# Schematic_SF_13_12_2020_V8.net
KiCad netlist of a schematic drawn in EAGLE
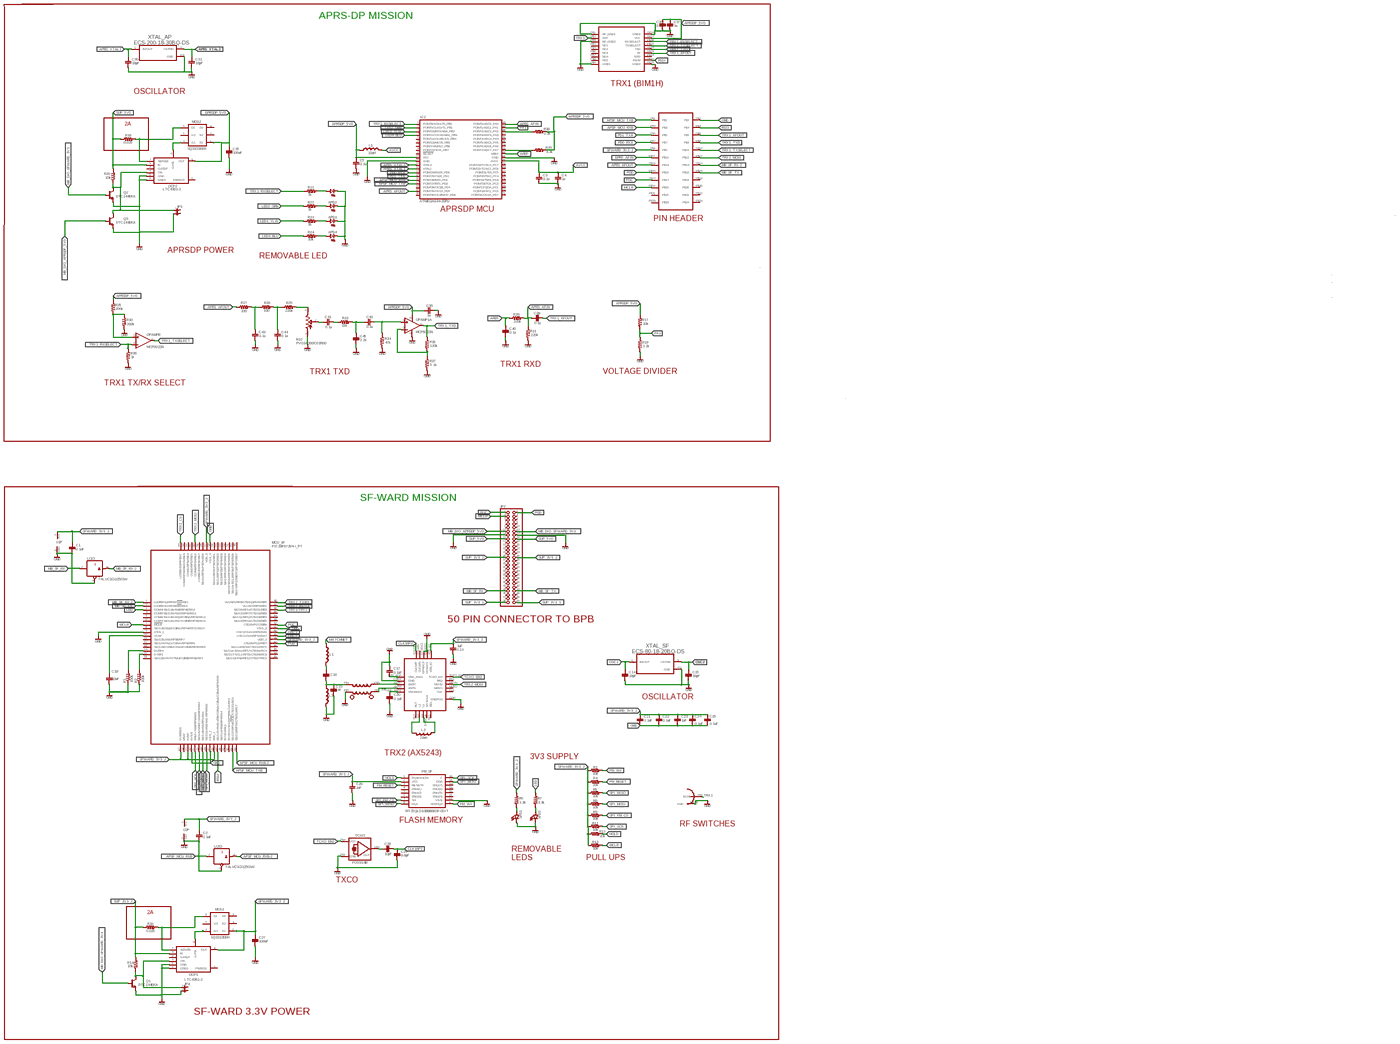
[diagram p0: schematic, sheet 1, overview]
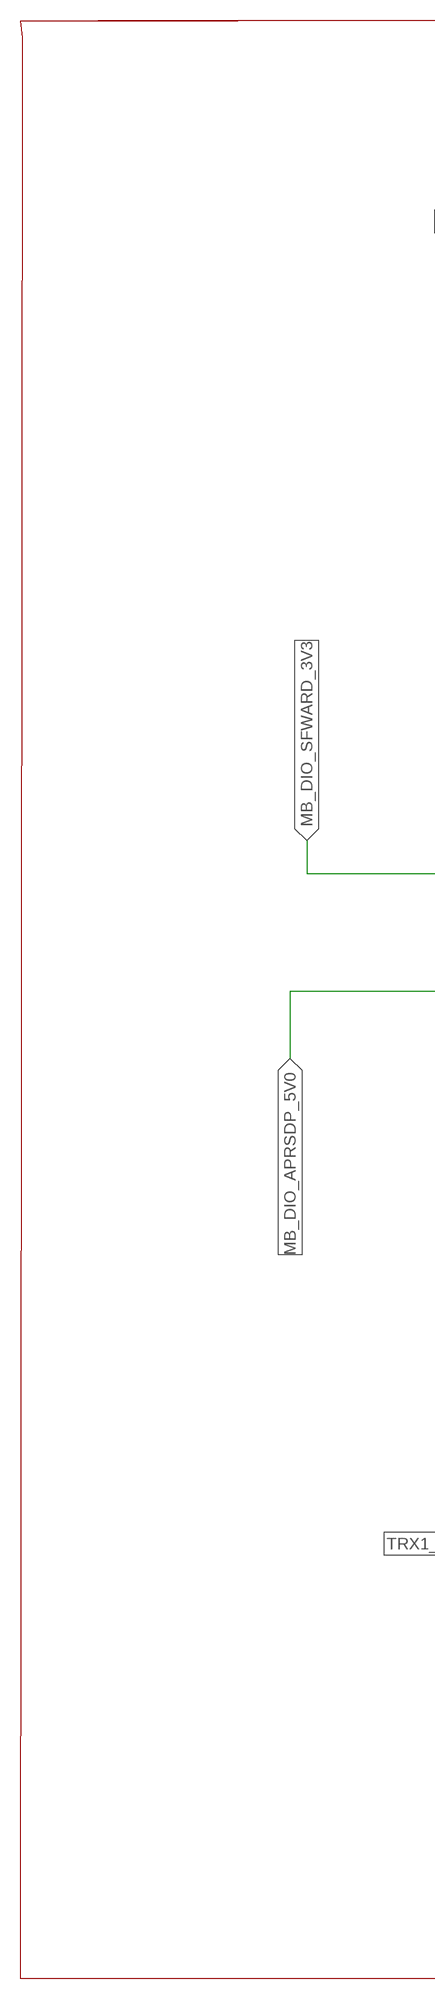
[diagram p1: schematic, sheet 1, part 1 of 4]
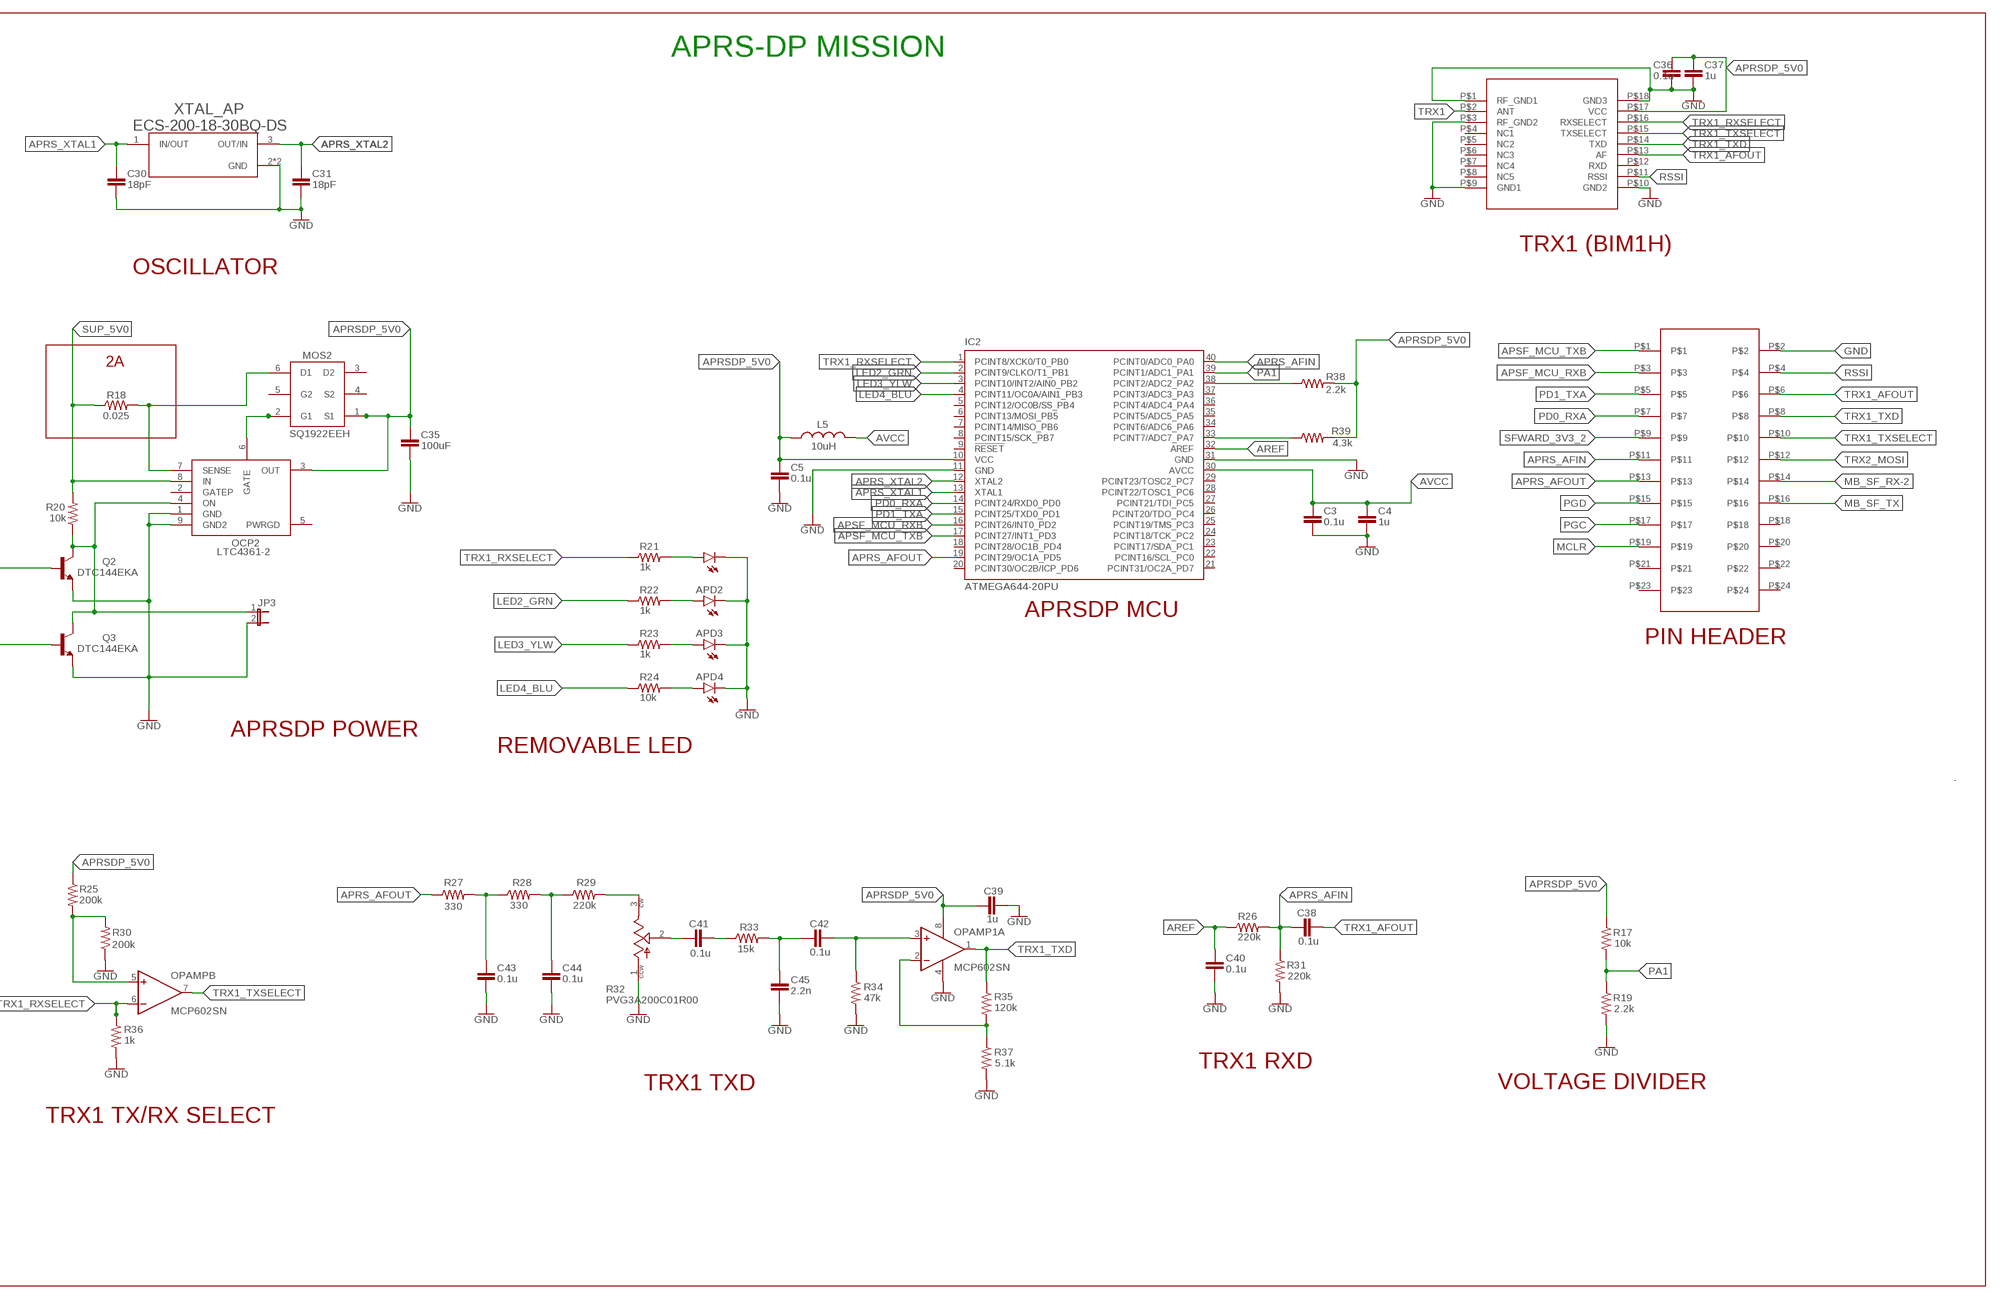
[diagram p2: schematic, sheet 1, part 2 of 4]
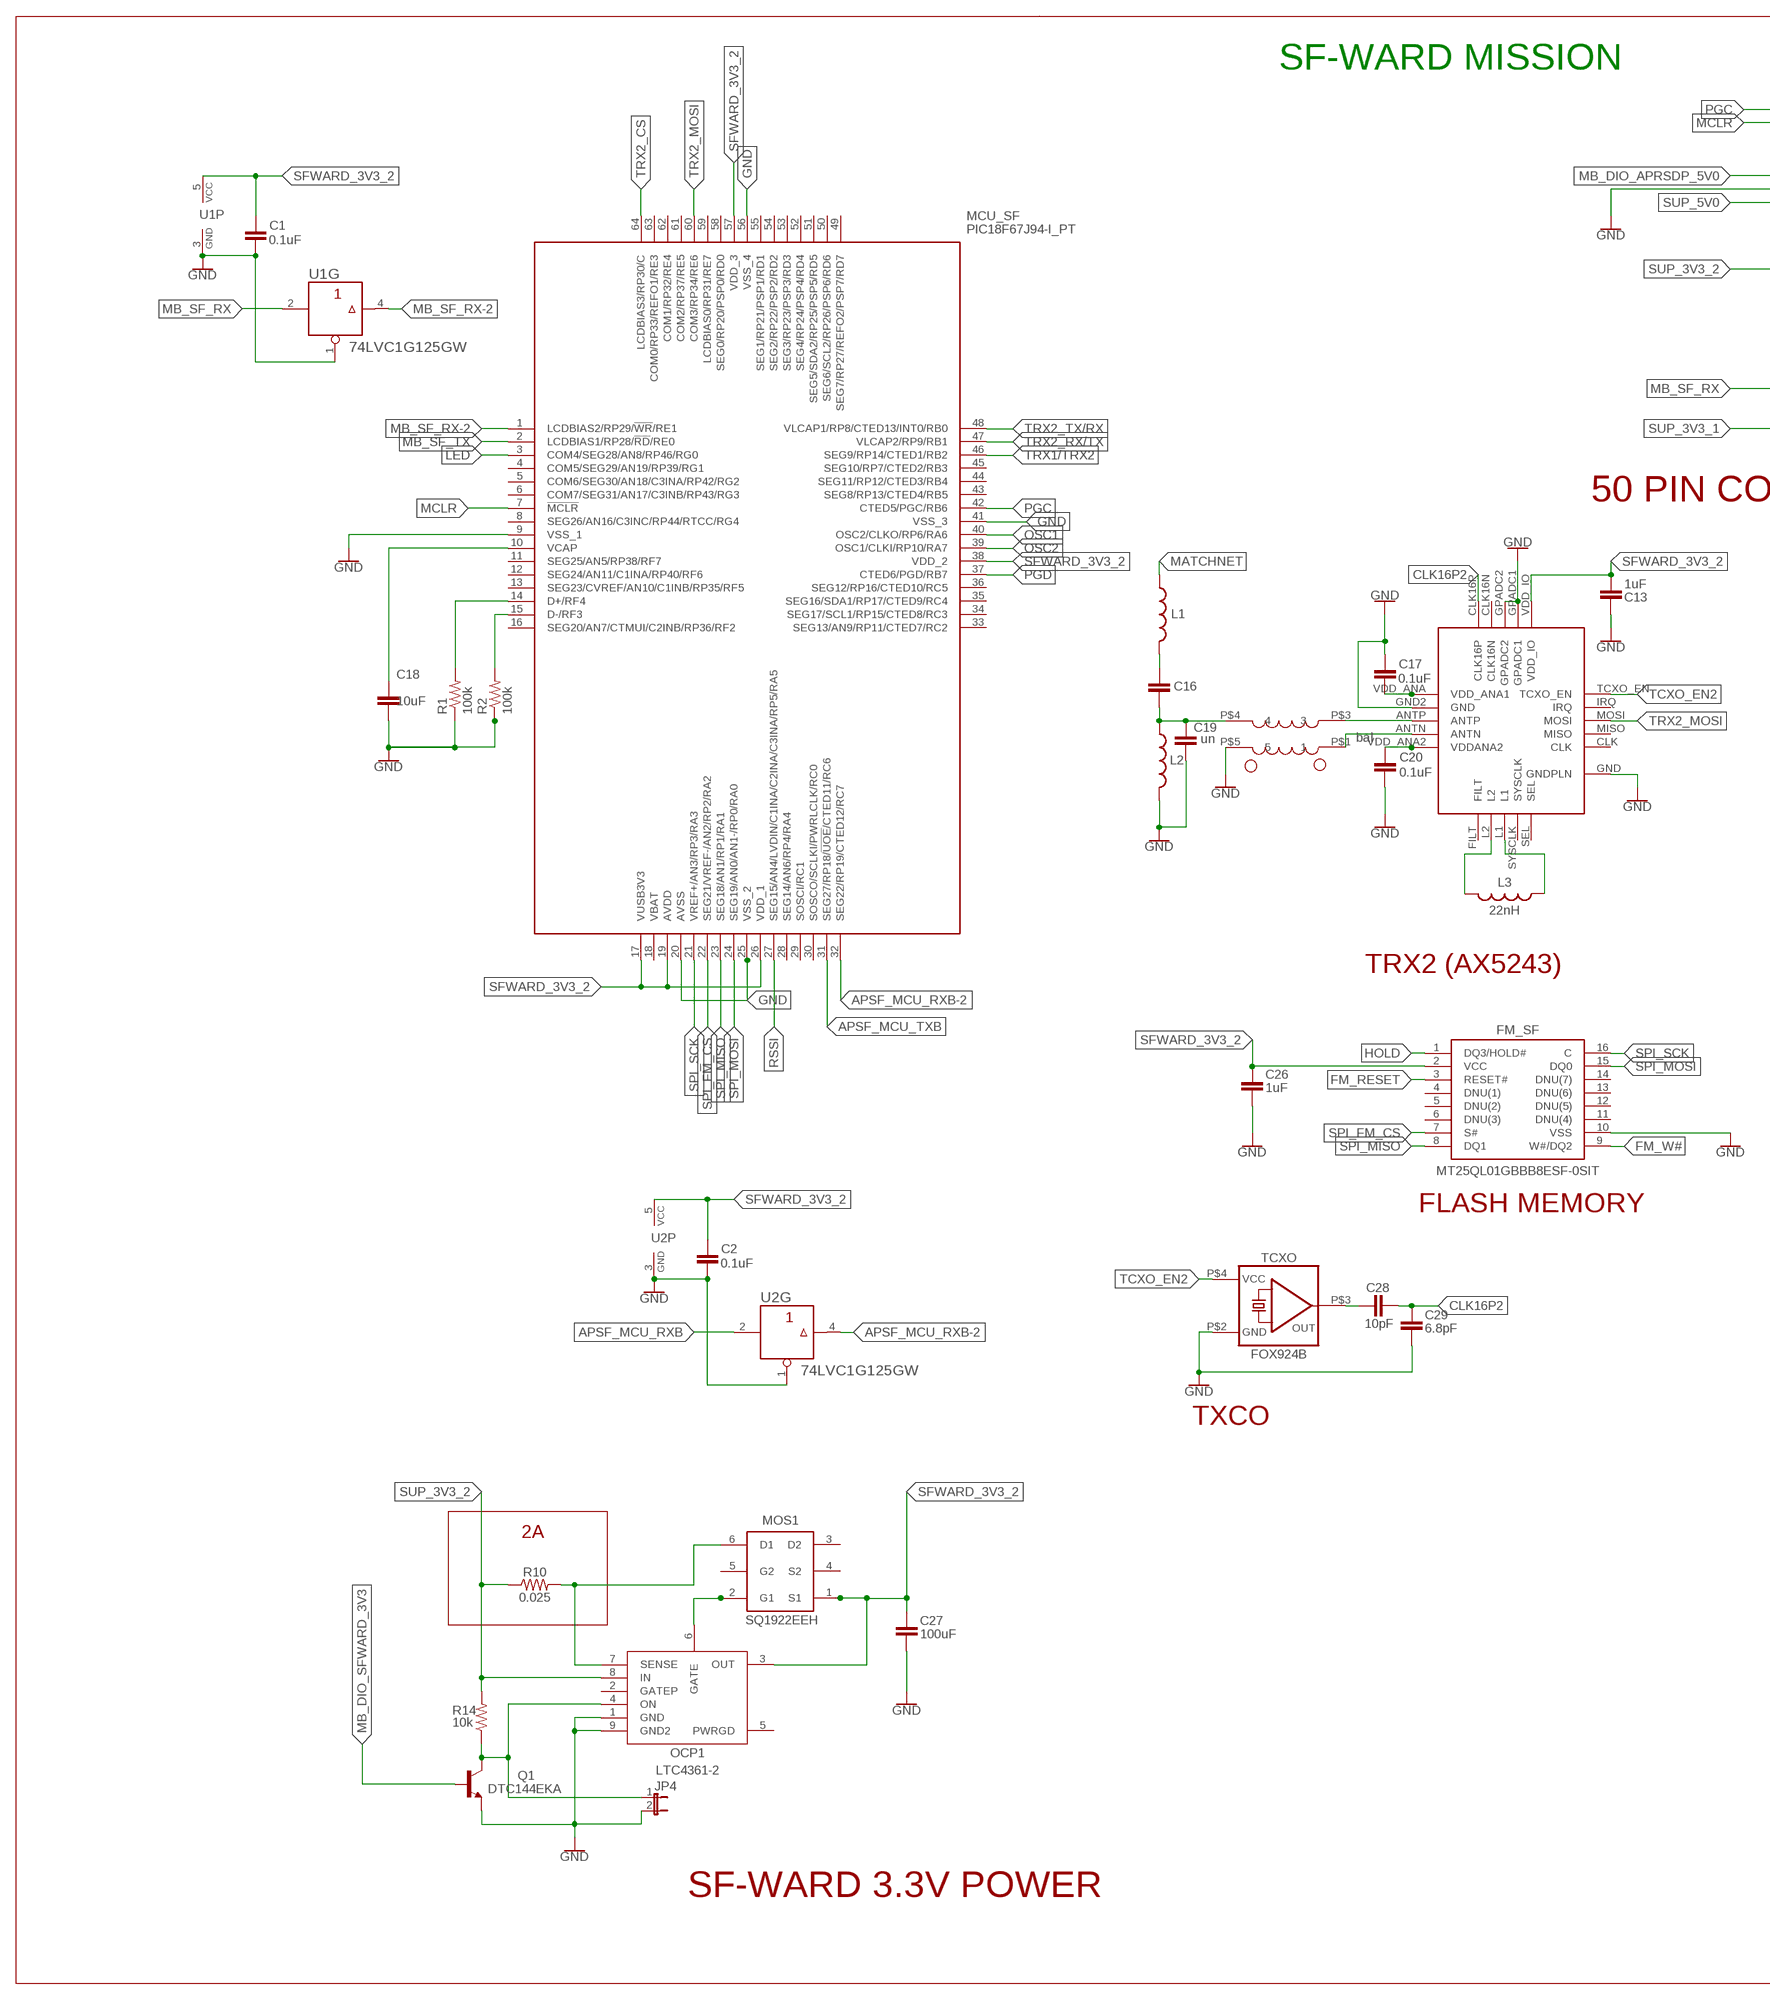
[diagram p3: schematic, sheet 1, part 3 of 4]
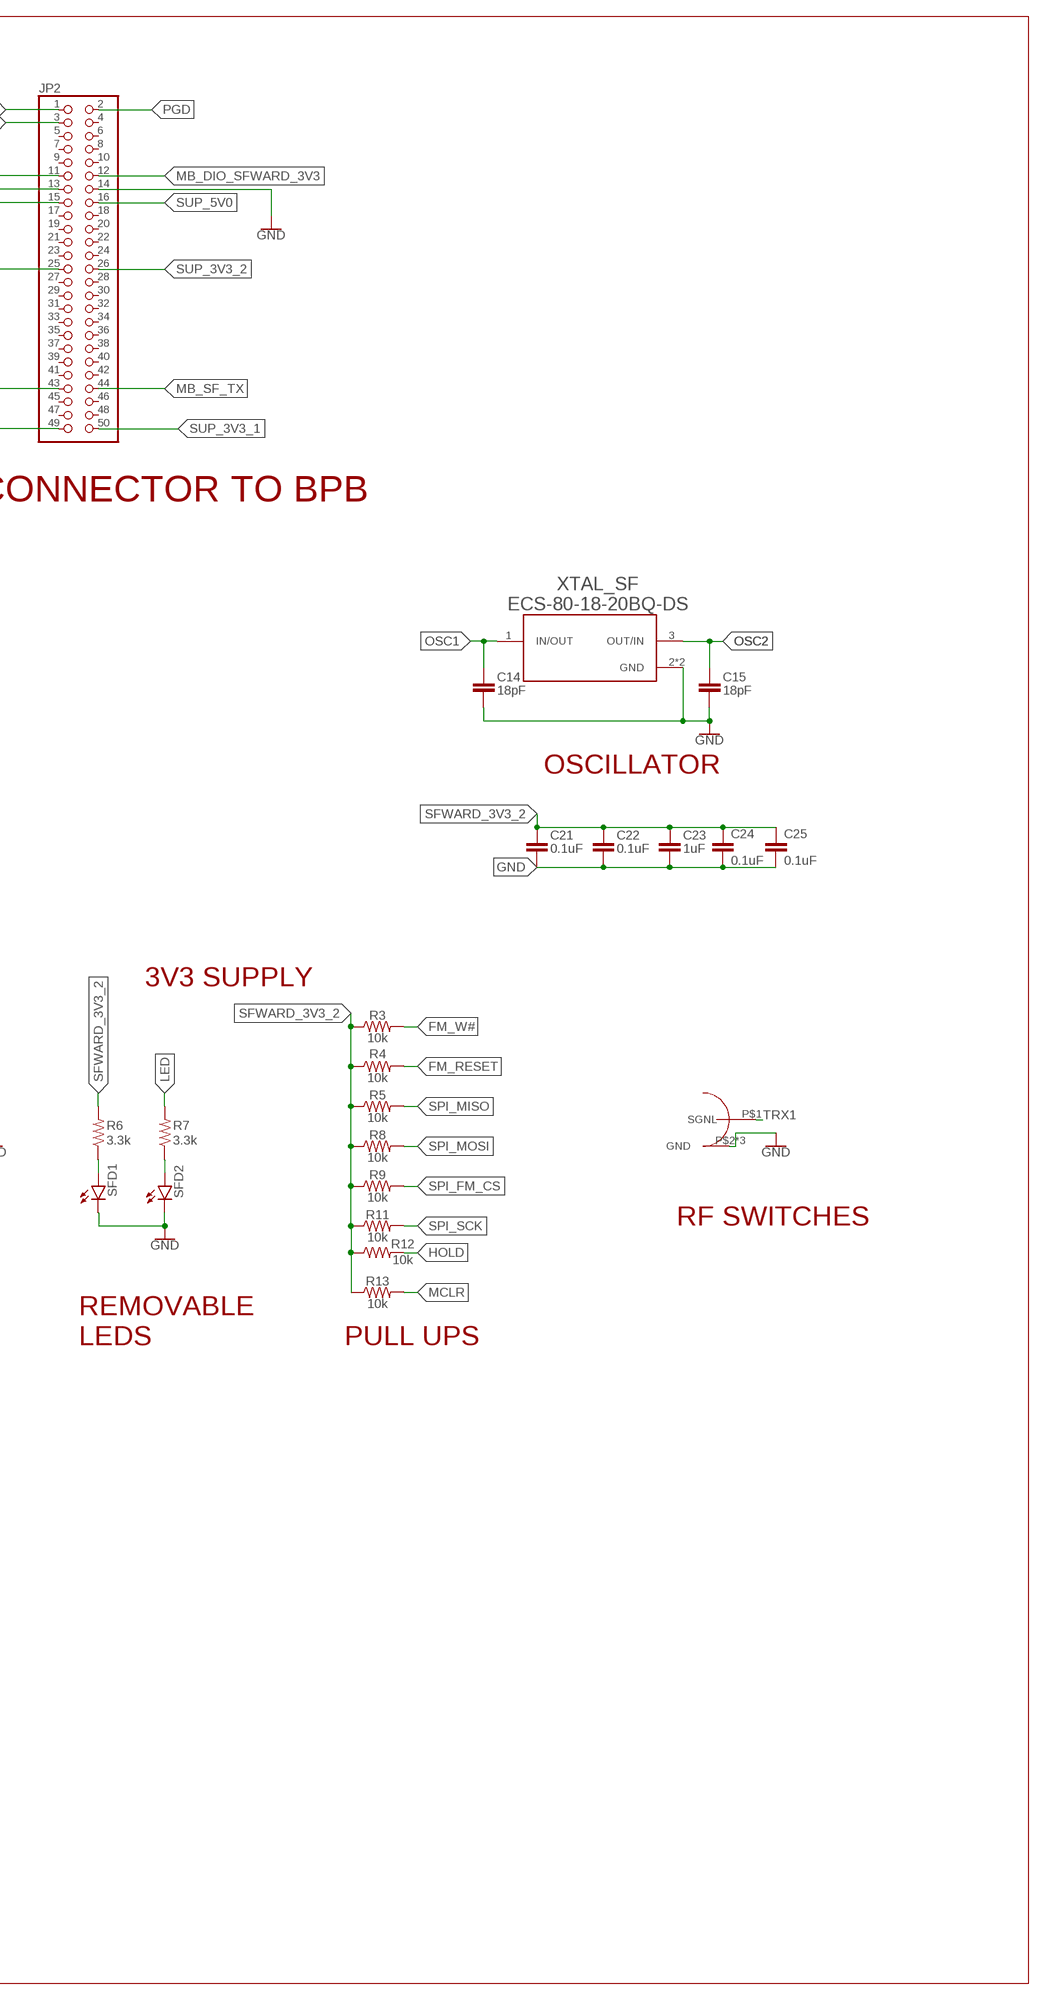
[diagram p4: schematic, sheet 1, part 4 of 4]

(export (version "E")
  (design (tool "Eeschema 10.0.6"))
  (components
    (comp (ref "APD1")
      (value "LEDSML0603")
      (footprint "eagle-import:SML0603")
      (libsource (lib "eagle-import") (part "LEDSML0603"))
    )
    (comp (ref "APD2")
      (value "LEDSML0603")
      (footprint "eagle-import:SML0603")
      (libsource (lib "eagle-import") (part "LEDSML0603"))
    )
    (comp (ref "APD3")
      (value "LEDSML0603")
      (footprint "eagle-import:SML0603")
      (libsource (lib "eagle-import") (part "LEDSML0603"))
    )
    (comp (ref "APD4")
      (value "LEDSML0603")
      (footprint "eagle-import:SML0603")
      (libsource (lib "eagle-import") (part "LEDSML0603"))
    )
    (comp (ref "BAL")
      (value "MABA-010245-BALUN")
      (footprint "eagle-import:MABA-010245-BALUN")
      (libsource (lib "eagle-import") (part "MABA-010245-BALUN"))
    )
    (comp (ref "C1")
      (value "0.1uF")
      (footprint "eagle-import:C0603")
      (libsource (lib "eagle-import") (part "CC0603"))
    )
    (comp (ref "C2")
      (value "0.1uF")
      (footprint "eagle-import:C0603")
      (libsource (lib "eagle-import") (part "CC0603"))
    )
    (comp (ref "C3")
      (value "0.1u")
      (footprint "eagle-import:C0603")
      (libsource (lib "eagle-import") (part "CC0603"))
    )
    (comp (ref "C4")
      (value "1u")
      (footprint "eagle-import:C0603")
      (libsource (lib "eagle-import") (part "CC0603"))
    )
    (comp (ref "C5")
      (value "0.1u")
      (footprint "eagle-import:C0603")
      (libsource (lib "eagle-import") (part "CC0603"))
    )
    (comp (ref "C13")
      (value "1uF")
      (footprint "eagle-import:C0603")
      (libsource (lib "eagle-import") (part "CC0603"))
    )
    (comp (ref "C14")
      (value "18pF")
      (footprint "eagle-import:C0603")
      (libsource (lib "eagle-import") (part "CC0603"))
    )
    (comp (ref "C15")
      (value "18pF")
      (footprint "eagle-import:C0603")
      (libsource (lib "eagle-import") (part "CC0603"))
    )
    (comp (ref "C16")
      (value "C-EUC0805")
      (footprint "eagle-import:C0805")
      (libsource (lib "eagle-import") (part "C-EUC0805"))
    )
    (comp (ref "C17")
      (value "0.1uF")
      (footprint "eagle-import:C0603")
      (libsource (lib "eagle-import") (part "CC0603"))
    )
    (comp (ref "C18")
      (value "10uF")
      (footprint "eagle-import:C0603")
      (libsource (lib "eagle-import") (part "C-EUC0603"))
    )
    (comp (ref "C19")
      (value "C-EUC0805")
      (footprint "eagle-import:C0805")
      (libsource (lib "eagle-import") (part "C-EUC0805"))
    )
    (comp (ref "C20")
      (value "0.1uF")
      (footprint "eagle-import:C0603")
      (libsource (lib "eagle-import") (part "CC0603"))
    )
    (comp (ref "C21")
      (value "0.1uF")
      (footprint "eagle-import:C0603")
      (libsource (lib "eagle-import") (part "C-EUC0603"))
    )
    (comp (ref "C22")
      (value "0.1uF")
      (footprint "eagle-import:C0603")
      (libsource (lib "eagle-import") (part "C-EUC0603"))
    )
    (comp (ref "C23")
      (value "1uF")
      (footprint "eagle-import:C0603")
      (libsource (lib "eagle-import") (part "C-EUC0603"))
    )
    (comp (ref "C24")
      (value "0.1uF")
      (footprint "eagle-import:C0603")
      (libsource (lib "eagle-import") (part "C-EUC0603"))
    )
    (comp (ref "C25")
      (value "0.1uF")
      (footprint "eagle-import:C0603")
      (libsource (lib "eagle-import") (part "C-EUC0603"))
    )
    (comp (ref "C26")
      (value "1uF")
      (footprint "eagle-import:C0603")
      (libsource (lib "eagle-import") (part "C-EUC0603"))
    )
    (comp (ref "C27")
      (value "100uF")
      (footprint "eagle-import:C0805")
      (libsource (lib "eagle-import") (part "C0805(2012)"))
    )
    (comp (ref "C28")
      (value "10pF")
      (footprint "eagle-import:C0603")
      (libsource (lib "eagle-import") (part "CC0603"))
    )
    (comp (ref "C29")
      (value "6.8pF")
      (footprint "eagle-import:C0603")
      (libsource (lib "eagle-import") (part "CC0603"))
    )
    (comp (ref "C30")
      (value "18pF")
      (footprint "eagle-import:C0603")
      (libsource (lib "eagle-import") (part "CC0603"))
    )
    (comp (ref "C31")
      (value "18pF")
      (footprint "eagle-import:C0603")
      (libsource (lib "eagle-import") (part "CC0603"))
    )
    (comp (ref "C35")
      (value "100uF")
      (footprint "eagle-import:C0805")
      (libsource (lib "eagle-import") (part "C0805(2012)"))
    )
    (comp (ref "C36")
      (value "0.1u")
      (footprint "eagle-import:C0603")
      (libsource (lib "eagle-import") (part "CC0603"))
    )
    (comp (ref "C37")
      (value "1u")
      (footprint "eagle-import:C0603")
      (libsource (lib "eagle-import") (part "CC0603"))
    )
    (comp (ref "C38")
      (value "0.1u")
      (footprint "eagle-import:C0603")
      (libsource (lib "eagle-import") (part "CC0603"))
    )
    (comp (ref "C39")
      (value "1u")
      (footprint "eagle-import:C0603")
      (libsource (lib "eagle-import") (part "CC0603"))
    )
    (comp (ref "C40")
      (value "0.1u")
      (footprint "eagle-import:C0603")
      (libsource (lib "eagle-import") (part "CC0603"))
    )
    (comp (ref "C41")
      (value "0.1u")
      (footprint "eagle-import:C0603")
      (libsource (lib "eagle-import") (part "CC0603"))
    )
    (comp (ref "C42")
      (value "0.1u")
      (footprint "eagle-import:C0603")
      (libsource (lib "eagle-import") (part "CC0603"))
    )
    (comp (ref "C43")
      (value "0.1u")
      (footprint "eagle-import:C0603")
      (libsource (lib "eagle-import") (part "CC0603"))
    )
    (comp (ref "C44")
      (value "0.1u")
      (footprint "eagle-import:C0603")
      (libsource (lib "eagle-import") (part "CC0603"))
    )
    (comp (ref "C45")
      (value "2.2n")
      (footprint "eagle-import:C0603")
      (libsource (lib "eagle-import") (part "CC0603"))
    )
    (comp (ref "FM_SF")
      (value "MT25QL01GBBB8ESF-0SIT")
      (footprint "eagle-import:SOIC127P1032X265-16N")
      (libsource (lib "eagle-import") (part "MT25QL01GBBB8ESF-0SIT"))
    )
    (comp (ref "IC2")
      (value "ATMEGA644-20PU")
      (footprint "eagle-import:DIL40")
      (libsource (lib "eagle-import") (part "ATMEGA644-PU20"))
    )
    (comp (ref "JP1")
      (value "RAB_ACCESS")
      (footprint "eagle-import:RAB_ACCESS")
      (libsource (lib "eagle-import") (part "RAB_ACCESS"))
    )
    (comp (ref "JP2")
      (value "PINHD-2X25_2.00")
      (footprint "eagle-import:2X25M")
      (libsource (lib "eagle-import") (part "PINHD-2X25_2.00"))
    )
    (comp (ref "JP3")
      (value "JP1E")
      (footprint "eagle-import:JP1")
      (libsource (lib "eagle-import") (part "JP1E"))
    )
    (comp (ref "JP4")
      (value "JP1E")
      (footprint "eagle-import:JP1")
      (libsource (lib "eagle-import") (part "JP1E"))
    )
    (comp (ref "L1")
      (value "L-USL2012C")
      (footprint "eagle-import:L2012C")
      (libsource (lib "eagle-import") (part "L-USL2012C"))
    )
    (comp (ref "L2")
      (value "L-USL2012C")
      (footprint "eagle-import:L2012C")
      (libsource (lib "eagle-import") (part "L-USL2012C"))
    )
    (comp (ref "L3")
      (value "22nH")
      (footprint "eagle-import:L2012C")
      (libsource (lib "eagle-import") (part "L-USL2012C"))
    )
    (comp (ref "L5")
      (value "10uH")
      (footprint "eagle-import:L2012C")
      (libsource (lib "eagle-import") (part "L-USL2012C"))
    )
    (comp (ref "MCU_SF")
      (value "PIC18F67J94-I_PT")
      (footprint "eagle-import:QFP50P1200X1200X120-64N")
      (fields
        (field (name "MANUFACTURER_PART_NUMBER") "PIC18F67J94-I/PT")
        (field (name "MOUSER_PART_NUMBER") "579-PIC18F67J94-I/PT")
        (field (name "RS_PART_NUMBER") "1652172")
      )
      (libsource (lib "eagle-import") (part "PIC18F67J94-I_PT"))
    )
    (comp (ref "MOS1")
      (value "SQ1922EEH")
      (footprint "eagle-import:SOT65P210X110-6N")
      (libsource (lib "eagle-import") (part "SQ1922EEH"))
    )
    (comp (ref "MOS2")
      (value "SQ1922EEH")
      (footprint "eagle-import:SOT65P210X110-6N")
      (libsource (lib "eagle-import") (part "SQ1922EEH"))
    )
    (comp (ref "OCP1")
      (value "LTC4361-2")
      (footprint "eagle-import:DFN")
      (libsource (lib "eagle-import") (part "LTC4361-2"))
    )
    (comp (ref "OCP2")
      (value "LTC4361-2")
      (footprint "eagle-import:DFN")
      (libsource (lib "eagle-import") (part "LTC4361-2"))
    )
    (comp (ref "OPAMP")
      (value "MCP602SN")
      (footprint "eagle-import:SO08")
      (libsource (lib "eagle-import") (part "MCP602SN"))
    )
    (comp (ref "OPAMP1")
      (value "MCP602SN")
      (footprint "eagle-import:SO08")
      (libsource (lib "eagle-import") (part "MCP602SN"))
    )
    (comp (ref "Q1")
      (value "DTC144EKA")
      (footprint "eagle-import:SOT346-R")
      (libsource (lib "eagle-import") (part "DTC144EKA"))
    )
    (comp (ref "Q2")
      (value "DTC144EKA")
      (footprint "eagle-import:SOT346-R")
      (libsource (lib "eagle-import") (part "DTC144EKA"))
    )
    (comp (ref "Q3")
      (value "DTC144EKA")
      (footprint "eagle-import:SOT346-R")
      (libsource (lib "eagle-import") (part "DTC144EKA"))
    )
    (comp (ref "R1")
      (value "100k")
      (footprint "eagle-import:R0603")
      (libsource (lib "eagle-import") (part "R-US_R0603"))
    )
    (comp (ref "R2")
      (value "100k")
      (footprint "eagle-import:R0603")
      (libsource (lib "eagle-import") (part "R-US_R0603"))
    )
    (comp (ref "R3")
      (value "10k")
      (footprint "eagle-import:R0603")
      (libsource (lib "eagle-import") (part "R-US_R0603"))
    )
    (comp (ref "R4")
      (value "10k")
      (footprint "eagle-import:R0603")
      (libsource (lib "eagle-import") (part "R-US_R0603"))
    )
    (comp (ref "R5")
      (value "10k")
      (footprint "eagle-import:R0603")
      (libsource (lib "eagle-import") (part "R-US_R0603"))
    )
    (comp (ref "R6")
      (value "3.3k")
      (footprint "eagle-import:R0603")
      (libsource (lib "eagle-import") (part "R-US_R0603"))
    )
    (comp (ref "R7")
      (value "3.3k")
      (footprint "eagle-import:R0603")
      (libsource (lib "eagle-import") (part "R-US_R0603"))
    )
    (comp (ref "R8")
      (value "10k")
      (footprint "eagle-import:R0603")
      (libsource (lib "eagle-import") (part "R-US_R0603"))
    )
    (comp (ref "R9")
      (value "10k")
      (footprint "eagle-import:R0603")
      (libsource (lib "eagle-import") (part "R-US_R0603"))
    )
    (comp (ref "R10")
      (value "0.025")
      (footprint "eagle-import:R0805")
      (libsource (lib "eagle-import") (part "R0805(2012)"))
    )
    (comp (ref "R11")
      (value "10k")
      (footprint "eagle-import:R0603")
      (libsource (lib "eagle-import") (part "R-US_R0603"))
    )
    (comp (ref "R12")
      (value "10k")
      (footprint "eagle-import:R0603")
      (libsource (lib "eagle-import") (part "R-US_R0603"))
    )
    (comp (ref "R13")
      (value "10k")
      (footprint "eagle-import:R0603")
      (libsource (lib "eagle-import") (part "R-US_R0603"))
    )
    (comp (ref "R14")
      (value "10k")
      (footprint "eagle-import:R0603")
      (libsource (lib "eagle-import") (part "R-US_R0603"))
    )
    (comp (ref "R17")
      (value "10k")
      (footprint "eagle-import:R0603")
      (libsource (lib "eagle-import") (part "R-US_R0603"))
    )
    (comp (ref "R18")
      (value "0.025")
      (footprint "eagle-import:R0805")
      (libsource (lib "eagle-import") (part "R-US_R0805"))
    )
    (comp (ref "R19")
      (value "2.2k")
      (footprint "eagle-import:R0603")
      (libsource (lib "eagle-import") (part "R-US_R0603"))
    )
    (comp (ref "R20")
      (value "10k")
      (footprint "eagle-import:R0603")
      (libsource (lib "eagle-import") (part "R-US_R0603"))
    )
    (comp (ref "R21")
      (value "1k")
      (footprint "eagle-import:R0603")
      (libsource (lib "eagle-import") (part "R-US_R0603"))
    )
    (comp (ref "R22")
      (value "1k")
      (footprint "eagle-import:R0603")
      (libsource (lib "eagle-import") (part "R-US_R0603"))
    )
    (comp (ref "R23")
      (value "1k")
      (footprint "eagle-import:R0603")
      (libsource (lib "eagle-import") (part "R-US_R0603"))
    )
    (comp (ref "R24")
      (value "10k")
      (footprint "eagle-import:R0603")
      (libsource (lib "eagle-import") (part "R-US_R0603"))
    )
    (comp (ref "R25")
      (value "200k")
      (footprint "eagle-import:R0603")
      (libsource (lib "eagle-import") (part "R-US_R0603"))
    )
    (comp (ref "R26")
      (value "220k")
      (footprint "eagle-import:R0603")
      (libsource (lib "eagle-import") (part "R-US_R0603"))
    )
    (comp (ref "R27")
      (value "330")
      (footprint "eagle-import:R0603")
      (libsource (lib "eagle-import") (part "R-US_R0603"))
    )
    (comp (ref "R28")
      (value "330")
      (footprint "eagle-import:R0603")
      (libsource (lib "eagle-import") (part "R-US_R0603"))
    )
    (comp (ref "R29")
      (value "220k")
      (footprint "eagle-import:R0603")
      (libsource (lib "eagle-import") (part "R-US_R0603"))
    )
    (comp (ref "R30")
      (value "200k")
      (footprint "eagle-import:R0603")
      (libsource (lib "eagle-import") (part "R-US_R0603"))
    )
    (comp (ref "R31")
      (value "220k")
      (footprint "eagle-import:R0603")
      (libsource (lib "eagle-import") (part "R-US_R0603"))
    )
    (comp (ref "R32")
      (value "PVG3A200C01R00")
      (footprint "eagle-import:TRIM_PVG3A200C01R00")
      (fields (field (name "DIGI-KEY_PART_NUMBER") "490-2647-1-ND") (field (name "MF") "Bourns"))
      (libsource (lib "eagle-import") (part "PVG3A200C01R00"))
    )
    (comp (ref "R33")
      (value "15k")
      (footprint "eagle-import:R0603")
      (libsource (lib "eagle-import") (part "R-US_R0603"))
    )
    (comp (ref "R34")
      (value "47k")
      (footprint "eagle-import:R0603")
      (libsource (lib "eagle-import") (part "R-US_R0603"))
    )
    (comp (ref "R35")
      (value "120k")
      (footprint "eagle-import:R0603")
      (libsource (lib "eagle-import") (part "R-US_R0603"))
    )
    (comp (ref "R36")
      (value "1k")
      (footprint "eagle-import:R0603")
      (libsource (lib "eagle-import") (part "R-US_R0603"))
    )
    (comp (ref "R37")
      (value "5.1k")
      (footprint "eagle-import:R0603")
      (libsource (lib "eagle-import") (part "R-US_R0603"))
    )
    (comp (ref "R38")
      (value "2.2k")
      (footprint "eagle-import:R0603")
      (libsource (lib "eagle-import") (part "R-US_R0603"))
    )
    (comp (ref "R39")
      (value "4.3k")
      (footprint "eagle-import:R0603")
      (libsource (lib "eagle-import") (part "R-US_R0603"))
    )
    (comp (ref "RFCON")
      (value "MMCX_908_222101T")
      (footprint "eagle-import:MMCX_908_222101T")
      (libsource (lib "eagle-import") (part "MMCX_908_222101T"))
    )
    (comp (ref "SFD1")
      (value "LEDCHIPLED_0603")
      (footprint "eagle-import:CHIPLED_0603")
      (libsource (lib "eagle-import") (part "LEDCHIPLED_0603"))
    )
    (comp (ref "SFD2")
      (value "LEDCHIPLED_0603")
      (footprint "eagle-import:CHIPLED_0603")
      (libsource (lib "eagle-import") (part "LEDCHIPLED_0603"))
    )
    (comp (ref "TCXO")
      (value "FOX924B")
      (footprint "eagle-import:FOX924B")
      (libsource (lib "eagle-import") (part "FOX924B"))
    )
    (comp (ref "TRX1")
      (value "BIM1H")
      (footprint "eagle-import:BIM1H")
      (libsource (lib "eagle-import") (part "BIM1H"))
    )
    (comp (ref "TRX2")
      (value "AX5243")
      (footprint "eagle-import:AX5243")
      (libsource (lib "eagle-import") (part "AX5243"))
    )
    (comp (ref "U1")
      (value "74LVC1G125GW")
      (footprint "eagle-import:SOT353-1")
      (libsource (lib "eagle-import") (part "74LVC1G125GW"))
    )
    (comp (ref "U2")
      (value "74LVC1G125GW")
      (footprint "eagle-import:SOT353-1")
      (libsource (lib "eagle-import") (part "74LVC1G125GW"))
    )
    (comp (ref "XTAL_AP")
      (value "ECS-200-18-30BQ-DS")
      (footprint "eagle-import:XTAL_ECS-200-18-30BQ-DS")
      (fields (field (name "DIGI-KEY_PART_NUMBER") "XC1997CT-ND") (field (name "MF") "ECS Inc."))
      (libsource (lib "eagle-import") (part "ECS-200-18-30BQ-DS"))
    )
    (comp (ref "XTAL_SF")
      (value "ECS-80-18-20BQ-DS")
      (footprint "eagle-import:XTAL_ECS-80-18-20BQ-DS")
      (fields (field (name "DIGI-KEY_PART_NUMBER") "XC2015CT-ND") (field (name "MF") "ECS Inc."))
      (libsource (lib "eagle-import") (part "ECS-80-18-20BQ-DS"))
    )
  )
  (nets
    (net (code "1") (name "APRSDP_5V0") (class "Default")
      (node (ref "C35") (pin "1") (pinfunction "1_1") (pintype "passive"))
      (node (ref "C36") (pin "1") (pinfunction "1_1") (pintype "passive"))
      (node (ref "C37") (pin "1") (pinfunction "1_1") (pintype "passive"))
      (node (ref "C39") (pin "1") (pinfunction "1_1") (pintype "passive"))
      (node (ref "C5") (pin "2") (pinfunction "2_2") (pintype "passive"))
      (node (ref "IC2") (pin "10") (pinfunction "VCC_10") (pintype "power_in"))
      (node (ref "L5") (pin "1") (pinfunction "1_1") (pintype "passive"))
      (node (ref "MOS2") (pin "1") (pinfunction "S1_1") (pintype "input"))
      (node (ref "OCP2") (pin "3") (pinfunction "OUT_3") (pintype "bidirectional"))
      (node (ref "OPAMP1") (pin "8") (pinfunction "V+_8") (pintype "power_in"))
      (node (ref "R17") (pin "1") (pinfunction "1_1") (pintype "passive"))
      (node (ref "R25") (pin "1") (pinfunction "1_1") (pintype "passive"))
      (node (ref "R38") (pin "2") (pinfunction "2_2") (pintype "passive"))
      (node (ref "R39") (pin "2") (pinfunction "2_2") (pintype "passive"))
      (node (ref "TRX1") (pin "P$17") (pinfunction "VCC_P$17") (pintype "bidirectional"))
    )
    (net (code "2") (name "APRS_AFIN") (class "Default")
      (node (ref "C38") (pin "1") (pinfunction "1_1") (pintype "passive"))
      (node (ref "IC2") (pin "40") (pinfunction "PCINT0/ADC0_PA0_40") (pintype "bidirectional"))
      (node (ref "JP1") (pin "P$11") (pinfunction "P$11_P$11") (pintype "bidirectional"))
      (node (ref "R26") (pin "2") (pinfunction "2_2") (pintype "passive"))
      (node (ref "R31") (pin "1") (pinfunction "1_1") (pintype "passive"))
    )
    (net (code "3") (name "APRS_AFOUT") (class "Default")
      (node (ref "IC2") (pin "19") (pinfunction "PCINT29/OC1A_PD5_19") (pintype "bidirectional"))
      (node (ref "JP1") (pin "P$13") (pinfunction "P$13_P$13") (pintype "bidirectional"))
      (node (ref "R27") (pin "1") (pinfunction "1_1") (pintype "passive"))
    )
    (net (code "4") (name "APRS_XTAL1") (class "Default")
      (node (ref "C30") (pin "1") (pinfunction "1_1") (pintype "passive"))
      (node (ref "IC2") (pin "13") (pinfunction "XTAL1_13") (pintype "input"))
      (node (ref "XTAL_AP") (pin "1") (pinfunction "IN/OUT_1") (pintype "bidirectional"))
    )
    (net (code "5") (name "APRS_XTAL2") (class "Default")
      (node (ref "C31") (pin "1") (pinfunction "1_1") (pintype "passive"))
      (node (ref "IC2") (pin "12") (pinfunction "XTAL2_12") (pintype "output"))
      (node (ref "XTAL_AP") (pin "3") (pinfunction "OUT/IN_3") (pintype "bidirectional"))
    )
    (net (code "6") (name "APSF_MCU_RXB") (class "Default")
      (node (ref "IC2") (pin "16") (pinfunction "PCINT26/INT0_PD2_16") (pintype "bidirectional"))
      (node (ref "JP1") (pin "P$3") (pinfunction "P$3_P$3") (pintype "bidirectional"))
      (node (ref "U2") (pin "2") (pinfunction "A_2") (pintype "input"))
    )
    (net (code "7") (name "APSF_MCU_RXB-2") (class "Default")
      (node (ref "MCU_SF") (pin "32") (pinfunction "SEG22/RP19/CTED12/RC7_32") (pintype "bidirectional"))
      (node (ref "U2") (pin "4") (pinfunction "Y_4") (pintype "output"))
    )
    (net (code "8") (name "APSF_MCU_TXB") (class "Default")
      (node (ref "IC2") (pin "17") (pinfunction "PCINT27/INT1_PD3_17") (pintype "bidirectional"))
      (node (ref "JP1") (pin "P$1") (pinfunction "P$1_P$1") (pintype "bidirectional"))
      (node (ref "MCU_SF") (pin "31") (pinfunction "SEG27/RP18/~{UOE}/CTED11/RC6_31") (pintype "bidirectional"))
    )
    (net (code "9") (name "AREF") (class "Default")
      (node (ref "C40") (pin "1") (pinfunction "1_1") (pintype "passive"))
      (node (ref "IC2") (pin "32") (pinfunction "AREF_32") (pintype "passive"))
      (node (ref "R26") (pin "1") (pinfunction "1_1") (pintype "passive"))
    )
    (net (code "10") (name "AVCC") (class "Default")
      (node (ref "C3") (pin "1") (pinfunction "1_1") (pintype "passive"))
      (node (ref "C4") (pin "1") (pinfunction "1_1") (pintype "passive"))
      (node (ref "IC2") (pin "30") (pinfunction "AVCC_30") (pintype "power_in"))
      (node (ref "L5") (pin "2") (pinfunction "2_2") (pintype "passive"))
    )
    (net (code "11") (name "CLK16P2") (class "Default")
      (node (ref "C28") (pin "2") (pinfunction "2_2") (pintype "passive"))
      (node (ref "C29") (pin "1") (pinfunction "1_1") (pintype "passive"))
      (node (ref "TRX2") (pin "CLK16P") (pinfunction "CLK16P_CLK16P") (pintype "bidirectional"))
    )
    (net (code "12") (name "FM_RESET") (class "Default")
      (node (ref "FM_SF") (pin "3") (pinfunction "RESET#_3") (pintype "input"))
      (node (ref "R4") (pin "2") (pinfunction "2_2") (pintype "passive"))
    )
    (net (code "13") (name "FM_W#") (class "Default")
      (node (ref "FM_SF") (pin "9") (pinfunction "W#/DQ2_9") (pintype "input"))
      (node (ref "R3") (pin "2") (pinfunction "2_2") (pintype "passive"))
    )
    (net (code "14") (name "GND") (class "Default")
      (node (ref "APD1") (pin "C") (pinfunction "C_C") (pintype "passive"))
      (node (ref "APD2") (pin "C") (pinfunction "C_C") (pintype "passive"))
      (node (ref "APD3") (pin "C") (pinfunction "C_C") (pintype "passive"))
      (node (ref "APD4") (pin "C") (pinfunction "C_C") (pintype "passive"))
      (node (ref "BAL") (pin "P$5") (pinfunction "5_P$5") (pintype "bidirectional"))
      (node (ref "C1") (pin "1") (pinfunction "1_1") (pintype "passive"))
      (node (ref "C13") (pin "1") (pinfunction "1_1") (pintype "passive"))
      (node (ref "C14") (pin "2") (pinfunction "2_2") (pintype "passive"))
      (node (ref "C15") (pin "2") (pinfunction "2_2") (pintype "passive"))
      (node (ref "C17") (pin "2") (pinfunction "2_2") (pintype "passive"))
      (node (ref "C18") (pin "2") (pinfunction "2_2") (pintype "passive"))
      (node (ref "C19") (pin "2") (pinfunction "2_2") (pintype "passive"))
      (node (ref "C2") (pin "1") (pinfunction "1_1") (pintype "passive"))
      (node (ref "C20") (pin "2") (pinfunction "2_2") (pintype "passive"))
      (node (ref "C21") (pin "2") (pinfunction "2_2") (pintype "passive"))
      (node (ref "C22") (pin "2") (pinfunction "2_2") (pintype "passive"))
      (node (ref "C23") (pin "2") (pinfunction "2_2") (pintype "passive"))
      (node (ref "C24") (pin "2") (pinfunction "2_2") (pintype "passive"))
      (node (ref "C25") (pin "2") (pinfunction "2_2") (pintype "passive"))
      (node (ref "C26") (pin "2") (pinfunction "2_2") (pintype "passive"))
      (node (ref "C27") (pin "2") (pinfunction "2_2") (pintype "passive"))
      (node (ref "C29") (pin "2") (pinfunction "2_2") (pintype "passive"))
      (node (ref "C3") (pin "2") (pinfunction "2_2") (pintype "passive"))
      (node (ref "C30") (pin "2") (pinfunction "2_2") (pintype "passive"))
      (node (ref "C31") (pin "2") (pinfunction "2_2") (pintype "passive"))
      (node (ref "C35") (pin "2") (pinfunction "2_2") (pintype "passive"))
      (node (ref "C36") (pin "2") (pinfunction "2_2") (pintype "passive"))
      (node (ref "C37") (pin "2") (pinfunction "2_2") (pintype "passive"))
      (node (ref "C39") (pin "2") (pinfunction "2_2") (pintype "passive"))
      (node (ref "C4") (pin "2") (pinfunction "2_2") (pintype "passive"))
      (node (ref "C40") (pin "2") (pinfunction "2_2") (pintype "passive"))
      (node (ref "C43") (pin "2") (pinfunction "2_2") (pintype "passive"))
      (node (ref "C44") (pin "2") (pinfunction "2_2") (pintype "passive"))
      (node (ref "C45") (pin "2") (pinfunction "2_2") (pintype "passive"))
      (node (ref "C5") (pin "1") (pinfunction "1_1") (pintype "passive"))
      (node (ref "FM_SF") (pin "10") (pinfunction "VSS_10") (pintype "input"))
      (node (ref "IC2") (pin "11") (pinfunction "GND_11") (pintype "power_in"))
      (node (ref "IC2") (pin "31") (pinfunction "GND_31") (pintype "power_in"))
      (node (ref "JP1") (pin "P$2") (pinfunction "P$2_P$2") (pintype "bidirectional"))
      (node (ref "JP2") (pin "13") (pinfunction "13_13") (pintype "passive"))
      (node (ref "JP2") (pin "14") (pinfunction "14_14") (pintype "passive"))
      (node (ref "JP3") (pin "2") (pinfunction "2_2") (pintype "passive"))
      (node (ref "JP4") (pin "2") (pinfunction "2_2") (pintype "passive"))
      (node (ref "L2") (pin "2") (pinfunction "2_2") (pintype "passive"))
      (node (ref "MCU_SF") (pin "20") (pinfunction "AVSS_20") (pintype "bidirectional"))
      (node (ref "MCU_SF") (pin "25") (pinfunction "VSS_2_25") (pintype "bidirectional"))
      (node (ref "MCU_SF") (pin "41") (pinfunction "VSS_3_41") (pintype "bidirectional"))
      (node (ref "MCU_SF") (pin "56") (pinfunction "VSS_4_56") (pintype "bidirectional"))
      (node (ref "MCU_SF") (pin "9") (pinfunction "VSS_1_9") (pintype "bidirectional"))
      (node (ref "OCP1") (pin "1") (pinfunction "GND_1") (pintype "bidirectional"))
      (node (ref "OCP1") (pin "9") (pinfunction "GND2_9") (pintype "bidirectional"))
      (node (ref "OCP2") (pin "1") (pinfunction "GND_1") (pintype "bidirectional"))
      (node (ref "OCP2") (pin "9") (pinfunction "GND2_9") (pintype "bidirectional"))
      (node (ref "OPAMP1") (pin "4") (pinfunction "V-_4") (pintype "power_in"))
      (node (ref "Q1") (pin "1") (pinfunction "E_1") (pintype "passive"))
      (node (ref "Q2") (pin "1") (pinfunction "E_1") (pintype "passive"))
      (node (ref "Q3") (pin "1") (pinfunction "E_1") (pintype "passive"))
      (node (ref "R1") (pin "1") (pinfunction "1_1") (pintype "passive"))
      (node (ref "R19") (pin "2") (pinfunction "2_2") (pintype "passive"))
      (node (ref "R2") (pin "1") (pinfunction "1_1") (pintype "passive"))
      (node (ref "R30") (pin "1") (pinfunction "1_1") (pintype "passive"))
      (node (ref "R31") (pin "2") (pinfunction "2_2") (pintype "passive"))
      (node (ref "R32") (pin "1") (pinfunction "CCW_1") (pintype "passive"))
      (node (ref "R34") (pin "2") (pinfunction "2_2") (pintype "passive"))
      (node (ref "R36") (pin "2") (pinfunction "2_2") (pintype "passive"))
      (node (ref "R37") (pin "2") (pinfunction "2_2") (pintype "passive"))
      (node (ref "RFCON") (pin "P$2") (pinfunction "GND_P$2") (pintype "bidirectional"))
      (node (ref "RFCON") (pin "P$3") (pinfunction "GND_P$3") (pintype "bidirectional"))
      (node (ref "RFCON") (pin "P$4") (pinfunction "GND_P$4") (pintype "bidirectional"))
      (node (ref "SFD1") (pin "C") (pinfunction "C_C") (pintype "passive"))
      (node (ref "SFD2") (pin "C") (pinfunction "C_C") (pintype "passive"))
      (node (ref "TCXO") (pin "P$2") (pinfunction "GND_P$2") (pintype "power_in"))
      (node (ref "TRX1") (pin "P$1") (pinfunction "RF_GND1_P$1") (pintype "bidirectional"))
      (node (ref "TRX1") (pin "P$10") (pinfunction "GND2_P$10") (pintype "bidirectional"))
      (node (ref "TRX1") (pin "P$18") (pinfunction "GND3_P$18") (pintype "bidirectional"))
      (node (ref "TRX1") (pin "P$3") (pinfunction "RF_GND2_P$3") (pintype "bidirectional"))
      (node (ref "TRX1") (pin "P$9") (pinfunction "GND1_P$9") (pintype "bidirectional"))
      (node (ref "TRX2") (pin "GND") (pinfunction "GNDPLN_GND") (pintype "bidirectional"))
      (node (ref "TRX2") (pin "GND2") (pinfunction "GND_GND2") (pintype "bidirectional"))
      (node (ref "TRX2") (pin "GPADC1") (pinfunction "GPADC1_GPADC1") (pintype "bidirectional"))
      (node (ref "TRX2") (pin "GPADC2") (pinfunction "GPADC2_GPADC2") (pintype "bidirectional"))
      (node (ref "U1") (pin "1") (pinfunction "OEN_1") (pintype "input"))
      (node (ref "U1") (pin "3") (pinfunction "GND_3") (pintype "power_in"))
      (node (ref "U2") (pin "1") (pinfunction "OEN_1") (pintype "input"))
      (node (ref "U2") (pin "3") (pinfunction "GND_3") (pintype "power_in"))
      (node (ref "XTAL_AP") (pin "2") (pinfunction "GND_2") (pintype "power_in"))
      (node (ref "XTAL_AP") (pin "4") (pinfunction "GND_4") (pintype "power_in"))
      (node (ref "XTAL_SF") (pin "2") (pinfunction "GND_2") (pintype "power_in"))
      (node (ref "XTAL_SF") (pin "4") (pinfunction "GND_4") (pintype "power_in"))
    )
    (net (code "15") (name "HOLD") (class "Default")
      (node (ref "FM_SF") (pin "1") (pinfunction "DQ3/HOLD#_1") (pintype "input"))
      (node (ref "R12") (pin "2") (pinfunction "2_2") (pintype "passive"))
    )
    (net (code "16") (name "LED") (class "Default")
      (node (ref "MCU_SF") (pin "3") (pinfunction "COM4/SEG28/AN8/RP46/RG0_3") (pintype "bidirectional"))
      (node (ref "R7") (pin "2") (pinfunction "2_2") (pintype "passive"))
    )
    (net (code "17") (name "LED2_GRN") (class "Default")
      (node (ref "IC2") (pin "2") (pinfunction "PCINT9/CLKO/T1_PB1_2") (pintype "bidirectional"))
      (node (ref "R22") (pin "1") (pinfunction "1_1") (pintype "passive"))
    )
    (net (code "18") (name "LED3_YLW") (class "Default")
      (node (ref "IC2") (pin "3") (pinfunction "PCINT10/INT2/AIN0_PB2_3") (pintype "bidirectional"))
      (node (ref "R23") (pin "1") (pinfunction "1_1") (pintype "passive"))
    )
    (net (code "19") (name "LED4_BLU") (class "Default")
      (node (ref "IC2") (pin "4") (pinfunction "PCINT11/OC0A/AIN1_PB3_4") (pintype "bidirectional"))
      (node (ref "R24") (pin "1") (pinfunction "1_1") (pintype "passive"))
    )
    (net (code "20") (name "MATCHNET") (class "Default")
      (node (ref "L1") (pin "1") (pinfunction "1_1") (pintype "passive"))
    )
    (net (code "21") (name "MB_DIO_APRSDP_5V0") (class "Default")
      (node (ref "JP2") (pin "11") (pinfunction "11_11") (pintype "passive"))
      (node (ref "Q3") (pin "2") (pinfunction "B_2") (pintype "passive"))
    )
    (net (code "22") (name "MB_DIO_SFWARD_3V3") (class "Default")
      (node (ref "JP2") (pin "12") (pinfunction "12_12") (pintype "passive"))
      (node (ref "Q1") (pin "2") (pinfunction "B_2") (pintype "passive"))
      (node (ref "Q2") (pin "2") (pinfunction "B_2") (pintype "passive"))
    )
    (net (code "23") (name "MB_SF_RX") (class "Default")
      (node (ref "JP2") (pin "43") (pinfunction "43_43") (pintype "passive"))
      (node (ref "U1") (pin "2") (pinfunction "A_2") (pintype "input"))
    )
    (net (code "24") (name "MB_SF_RX-2") (class "Default")
      (node (ref "JP1") (pin "P$14") (pinfunction "P$14_P$14") (pintype "bidirectional"))
      (node (ref "MCU_SF") (pin "1") (pinfunction "LCDBIAS2/RP29/~{WR}/RE1_1") (pintype "bidirectional"))
      (node (ref "U1") (pin "4") (pinfunction "Y_4") (pintype "output"))
    )
    (net (code "25") (name "MB_SF_TX") (class "Default")
      (node (ref "JP1") (pin "P$16") (pinfunction "P$16_P$16") (pintype "bidirectional"))
      (node (ref "JP2") (pin "44") (pinfunction "44_44") (pintype "passive"))
      (node (ref "MCU_SF") (pin "2") (pinfunction "LCDBIAS1/RP28/~{RD}/RE0_2") (pintype "bidirectional"))
    )
    (net (code "26") (name "MCLR") (class "Default")
      (node (ref "JP1") (pin "P$19") (pinfunction "P$19_P$19") (pintype "bidirectional"))
      (node (ref "JP2") (pin "3") (pinfunction "3_3") (pintype "passive"))
      (node (ref "MCU_SF") (pin "7") (pinfunction "~{MCLR}_7") (pintype "bidirectional"))
      (node (ref "R13") (pin "2") (pinfunction "2_2") (pintype "passive"))
    )
    (net (code "27") (name "Net-(APD1-PadA)") (class "Default")
      (node (ref "APD1") (pin "A") (pinfunction "A_A") (pintype "passive"))
      (node (ref "R21") (pin "2") (pinfunction "2_2") (pintype "passive"))
    )
    (net (code "28") (name "Net-(APD2-PadA)") (class "Default")
      (node (ref "APD2") (pin "A") (pinfunction "A_A") (pintype "passive"))
      (node (ref "R22") (pin "2") (pinfunction "2_2") (pintype "passive"))
    )
    (net (code "29") (name "Net-(APD3-PadA)") (class "Default")
      (node (ref "APD3") (pin "A") (pinfunction "A_A") (pintype "passive"))
      (node (ref "R23") (pin "2") (pinfunction "2_2") (pintype "passive"))
    )
    (net (code "30") (name "Net-(APD4-PadA)") (class "Default")
      (node (ref "APD4") (pin "A") (pinfunction "A_A") (pintype "passive"))
      (node (ref "R24") (pin "2") (pinfunction "2_2") (pintype "passive"))
    )
    (net (code "31") (name "Net-(BAL-1)") (class "Default")
      (node (ref "BAL") (pin "P$1") (pinfunction "1_P$1") (pintype "bidirectional"))
      (node (ref "TRX2") (pin "ANTN") (pinfunction "ANTN_ANTN") (pintype "bidirectional"))
    )
    (net (code "32") (name "Net-(BAL-3)") (class "Default")
      (node (ref "BAL") (pin "P$3") (pinfunction "3_P$3") (pintype "bidirectional"))
      (node (ref "TRX2") (pin "ANTP") (pinfunction "ANTP_ANTP") (pintype "bidirectional"))
    )
    (net (code "33") (name "Net-(BAL-4)") (class "Default")
      (node (ref "BAL") (pin "P$4") (pinfunction "4_P$4") (pintype "bidirectional"))
      (node (ref "C16") (pin "2") (pinfunction "2_2") (pintype "passive"))
      (node (ref "C19") (pin "1") (pinfunction "1_1") (pintype "passive"))
      (node (ref "L2") (pin "1") (pinfunction "1_1") (pintype "passive"))
    )
    (net (code "34") (name "Net-(C16-Pad1)") (class "Default")
      (node (ref "C16") (pin "1") (pinfunction "1_1") (pintype "passive"))
      (node (ref "L1") (pin "2") (pinfunction "2_2") (pintype "passive"))
    )
    (net (code "35") (name "Net-(C41-Pad2)") (class "Default")
      (node (ref "C41") (pin "2") (pinfunction "2_2") (pintype "passive"))
      (node (ref "R33") (pin "1") (pinfunction "1_1") (pintype "passive"))
    )
    (net (code "36") (name "Net-(C42-Pad1)") (class "Default")
      (node (ref "C42") (pin "1") (pinfunction "1_1") (pintype "passive"))
      (node (ref "C45") (pin "1") (pinfunction "1_1") (pintype "passive"))
      (node (ref "R33") (pin "2") (pinfunction "2_2") (pintype "passive"))
    )
    (net (code "37") (name "Net-(C43-Pad1)") (class "Default")
      (node (ref "C43") (pin "1") (pinfunction "1_1") (pintype "passive"))
      (node (ref "R27") (pin "2") (pinfunction "2_2") (pintype "passive"))
      (node (ref "R28") (pin "1") (pinfunction "1_1") (pintype "passive"))
    )
    (net (code "38") (name "Net-(C44-Pad1)") (class "Default")
      (node (ref "C44") (pin "1") (pinfunction "1_1") (pintype "passive"))
      (node (ref "R28") (pin "2") (pinfunction "2_2") (pintype "passive"))
      (node (ref "R29") (pin "1") (pinfunction "1_1") (pintype "passive"))
    )
    (net (code "39") (name "Net-(IC2-PCINT2{slash}ADC2_PA2)") (class "Default")
      (node (ref "IC2") (pin "38") (pinfunction "PCINT2/ADC2_PA2_38") (pintype "bidirectional"))
      (node (ref "R38") (pin "1") (pinfunction "1_1") (pintype "passive"))
    )
    (net (code "40") (name "Net-(IC2-PCINT7{slash}ADC7_PA7)") (class "Default")
      (node (ref "IC2") (pin "33") (pinfunction "PCINT7/ADC7_PA7_33") (pintype "bidirectional"))
      (node (ref "R39") (pin "1") (pinfunction "1_1") (pintype "passive"))
    )
    (net (code "41") (name "Net-(L3-Pad1)") (class "Default")
      (node (ref "L3") (pin "1") (pinfunction "1_1") (pintype "passive"))
      (node (ref "TRX2") (pin "L1") (pinfunction "L1_L1") (pintype "bidirectional"))
    )
    (net (code "42") (name "Net-(L3-Pad2)") (class "Default")
      (node (ref "L3") (pin "2") (pinfunction "2_2") (pintype "passive"))
      (node (ref "TRX2") (pin "L2") (pinfunction "L2_L2") (pintype "bidirectional"))
    )
    (net (code "43") (name "Net-(MCU_SF-D+{slash}RF4)") (class "Default")
      (node (ref "MCU_SF") (pin "14") (pinfunction "D+/RF4_14") (pintype "bidirectional"))
      (node (ref "R1") (pin "2") (pinfunction "2_2") (pintype "passive"))
    )
    (net (code "44") (name "Net-(MCU_SF-D-{slash}RF3)") (class "Default")
      (node (ref "MCU_SF") (pin "15") (pinfunction "D-/RF3_15") (pintype "bidirectional"))
      (node (ref "R2") (pin "2") (pinfunction "2_2") (pintype "passive"))
    )
    (net (code "45") (name "Net-(MCU_SF-VCAP)") (class "Default")
      (node (ref "C18") (pin "1") (pinfunction "1_1") (pintype "passive"))
      (node (ref "MCU_SF") (pin "10") (pinfunction "VCAP_10") (pintype "bidirectional"))
    )
    (net (code "46") (name "Net-(MOS1-D1)") (class "Default")
      (node (ref "MOS1") (pin "6") (pinfunction "D1_6") (pintype "input"))
      (node (ref "OCP1") (pin "7") (pinfunction "SENSE_7") (pintype "bidirectional"))
      (node (ref "R10") (pin "2") (pinfunction "2_2") (pintype "passive"))
    )
    (net (code "47") (name "Net-(MOS1-G1)") (class "Default")
      (node (ref "MOS1") (pin "2") (pinfunction "G1_2") (pintype "input"))
      (node (ref "OCP1") (pin "6") (pinfunction "GATE_6") (pintype "bidirectional"))
    )
    (net (code "48") (name "Net-(MOS2-D1)") (class "Default")
      (node (ref "MOS2") (pin "6") (pinfunction "D1_6") (pintype "input"))
      (node (ref "OCP2") (pin "7") (pinfunction "SENSE_7") (pintype "bidirectional"))
      (node (ref "R18") (pin "2") (pinfunction "2_2") (pintype "passive"))
    )
    (net (code "49") (name "Net-(MOS2-G1)") (class "Default")
      (node (ref "MOS2") (pin "2") (pinfunction "G1_2") (pintype "input"))
      (node (ref "OCP2") (pin "6") (pinfunction "GATE_6") (pintype "bidirectional"))
    )
    (net (code "50") (name "Net-(OCP1-ON)") (class "Default")
      (node (ref "JP4") (pin "1") (pinfunction "1_1") (pintype "passive"))
      (node (ref "OCP1") (pin "4") (pinfunction "ON_4") (pintype "bidirectional"))
      (node (ref "Q1") (pin "3") (pinfunction "C_3") (pintype "passive"))
      (node (ref "R14") (pin "1") (pinfunction "1_1") (pintype "passive"))
    )
    (net (code "51") (name "Net-(OCP2-ON)") (class "Default")
      (node (ref "JP3") (pin "1") (pinfunction "1_1") (pintype "passive"))
      (node (ref "OCP2") (pin "4") (pinfunction "ON_4") (pintype "bidirectional"))
      (node (ref "Q2") (pin "3") (pinfunction "C_3") (pintype "passive"))
      (node (ref "Q3") (pin "3") (pinfunction "C_3") (pintype "passive"))
      (node (ref "R20") (pin "1") (pinfunction "1_1") (pintype "passive"))
    )
    (net (code "52") (name "Net-(OPAMP1A-+IN)") (class "Default")
      (node (ref "C42") (pin "2") (pinfunction "2_2") (pintype "passive"))
      (node (ref "OPAMP1") (pin "3") (pinfunction "+IN_3") (pintype "input"))
      (node (ref "R34") (pin "1") (pinfunction "1_1") (pintype "passive"))
    )
    (net (code "53") (name "Net-(OPAMP1A--IN)") (class "Default")
      (node (ref "OPAMP1") (pin "2") (pinfunction "-IN_2") (pintype "input"))
      (node (ref "R35") (pin "2") (pinfunction "2_2") (pintype "passive"))
      (node (ref "R37") (pin "1") (pinfunction "1_1") (pintype "passive"))
    )
    (net (code "54") (name "Net-(OPAMPB-+IN)") (class "Default")
      (node (ref "OPAMP") (pin "5") (pinfunction "+IN_5") (pintype "input"))
      (node (ref "R25") (pin "2") (pinfunction "2_2") (pintype "passive"))
      (node (ref "R30") (pin "2") (pinfunction "2_2") (pintype "passive"))
    )
    (net (code "55") (name "Net-(R6-Pad1)") (class "Default")
      (node (ref "R6") (pin "1") (pinfunction "1_1") (pintype "passive"))
      (node (ref "SFD1") (pin "A") (pinfunction "A_A") (pintype "passive"))
    )
    (net (code "56") (name "Net-(R7-Pad1)") (class "Default")
      (node (ref "R7") (pin "1") (pinfunction "1_1") (pintype "passive"))
      (node (ref "SFD2") (pin "A") (pinfunction "A_A") (pintype "passive"))
    )
    (net (code "57") (name "Net-(R32-CW)") (class "Default")
      (node (ref "R29") (pin "2") (pinfunction "2_2") (pintype "passive"))
      (node (ref "R32") (pin "3") (pinfunction "CW_3") (pintype "passive"))
    )
    (net (code "58") (name "Net-(R32-WIPER)") (class "Default")
      (node (ref "C41") (pin "1") (pinfunction "1_1") (pintype "passive"))
      (node (ref "R32") (pin "2") (pinfunction "WIPER_2") (pintype "passive"))
    )
    (net (code "59") (name "Net-(TCXO-OUT)") (class "Default")
      (node (ref "C28") (pin "1") (pinfunction "1_1") (pintype "passive"))
      (node (ref "TCXO") (pin "P$3") (pinfunction "OUT_P$3") (pintype "output"))
    )
    (net (code "60") (name "Net-(TRX2-VDDANA2)") (class "Default")
      (node (ref "C20") (pin "1") (pinfunction "1_1") (pintype "passive"))
      (node (ref "TRX2") (pin "VDD_ANA2") (pinfunction "VDDANA2_VDD_ANA2") (pintype "bidirectional"))
    )
    (net (code "61") (name "Net-(TRX2-VDD_ANA1)") (class "Default")
      (node (ref "C17") (pin "1") (pinfunction "1_1") (pintype "passive"))
      (node (ref "TRX2") (pin "VDD_ANA") (pinfunction "VDD_ANA1_VDD_ANA") (pintype "bidirectional"))
    )
    (net (code "62") (name "OSC1") (class "Default")
      (node (ref "C14") (pin "1") (pinfunction "1_1") (pintype "passive"))
      (node (ref "MCU_SF") (pin "40") (pinfunction "OSC2/CLKO/RP6/RA6_40") (pintype "bidirectional"))
      (node (ref "XTAL_SF") (pin "1") (pinfunction "IN/OUT_1") (pintype "bidirectional"))
    )
    (net (code "63") (name "OSC2") (class "Default")
      (node (ref "C15") (pin "1") (pinfunction "1_1") (pintype "passive"))
      (node (ref "MCU_SF") (pin "39") (pinfunction "OSC1/CLKI/RP10/RA7_39") (pintype "bidirectional"))
      (node (ref "XTAL_SF") (pin "3") (pinfunction "OUT/IN_3") (pintype "bidirectional"))
    )
    (net (code "64") (name "PA1") (class "Default")
      (node (ref "IC2") (pin "39") (pinfunction "PCINT1/ADC1_PA1_39") (pintype "bidirectional"))
      (node (ref "R17") (pin "2") (pinfunction "2_2") (pintype "passive"))
      (node (ref "R19") (pin "1") (pinfunction "1_1") (pintype "passive"))
    )
    (net (code "65") (name "PD0_RXA") (class "Default")
      (node (ref "IC2") (pin "14") (pinfunction "PCINT24/RXD0_PD0_14") (pintype "bidirectional"))
      (node (ref "JP1") (pin "P$7") (pinfunction "P$7_P$7") (pintype "bidirectional"))
    )
    (net (code "66") (name "PD1_TXA") (class "Default")
      (node (ref "IC2") (pin "15") (pinfunction "PCINT25/TXD0_PD1_15") (pintype "bidirectional"))
      (node (ref "JP1") (pin "P$5") (pinfunction "P$5_P$5") (pintype "bidirectional"))
    )
    (net (code "67") (name "PGC") (class "Default")
      (node (ref "JP1") (pin "P$17") (pinfunction "P$17_P$17") (pintype "bidirectional"))
      (node (ref "JP2") (pin "1") (pinfunction "1_1") (pintype "passive"))
      (node (ref "MCU_SF") (pin "42") (pinfunction "CTED5/PGC/RB6_42") (pintype "bidirectional"))
    )
    (net (code "68") (name "PGD") (class "Default")
      (node (ref "JP1") (pin "P$15") (pinfunction "P$15_P$15") (pintype "bidirectional"))
      (node (ref "JP2") (pin "2") (pinfunction "2_2") (pintype "passive"))
      (node (ref "MCU_SF") (pin "37") (pinfunction "CTED6/PGD/RB7_37") (pintype "bidirectional"))
    )
    (net (code "69") (name "RSSI") (class "Default")
      (node (ref "JP1") (pin "P$4") (pinfunction "P$4_P$4") (pintype "bidirectional"))
      (node (ref "MCU_SF") (pin "27") (pinfunction "SEG15/AN4/LVDIN/C1INA/C2INA/C3INA/RP5/RA5_27") (pintype "bidirectional"))
      (node (ref "TRX1") (pin "P$11") (pinfunction "RSSI_P$11") (pintype "bidirectional"))
    )
    (net (code "70") (name "SFWARD_3V3_2") (class "Default")
      (node (ref "C1") (pin "2") (pinfunction "2_2") (pintype "passive"))
      (node (ref "C13") (pin "2") (pinfunction "2_2") (pintype "passive"))
      (node (ref "C2") (pin "2") (pinfunction "2_2") (pintype "passive"))
      (node (ref "C21") (pin "1") (pinfunction "1_1") (pintype "passive"))
      (node (ref "C22") (pin "1") (pinfunction "1_1") (pintype "passive"))
      (node (ref "C23") (pin "1") (pinfunction "1_1") (pintype "passive"))
      (node (ref "C24") (pin "1") (pinfunction "1_1") (pintype "passive"))
      (node (ref "C25") (pin "1") (pinfunction "1_1") (pintype "passive"))
      (node (ref "C26") (pin "1") (pinfunction "1_1") (pintype "passive"))
      (node (ref "C27") (pin "1") (pinfunction "1_1") (pintype "passive"))
      (node (ref "FM_SF") (pin "2") (pinfunction "VCC_2") (pintype "input"))
      (node (ref "JP1") (pin "P$9") (pinfunction "P$9_P$9") (pintype "bidirectional"))
      (node (ref "MCU_SF") (pin "17") (pinfunction "VUSB3V3_17") (pintype "bidirectional"))
      (node (ref "MCU_SF") (pin "19") (pinfunction "AVDD_19") (pintype "bidirectional"))
      (node (ref "MCU_SF") (pin "26") (pinfunction "VDD_1_26") (pintype "bidirectional"))
      (node (ref "MCU_SF") (pin "38") (pinfunction "VDD_2_38") (pintype "bidirectional"))
      (node (ref "MCU_SF") (pin "57") (pinfunction "VDD_3_57") (pintype "bidirectional"))
      (node (ref "MOS1") (pin "1") (pinfunction "S1_1") (pintype "input"))
      (node (ref "OCP1") (pin "3") (pinfunction "OUT_3") (pintype "bidirectional"))
      (node (ref "R11") (pin "1") (pinfunction "1_1") (pintype "passive"))
      (node (ref "R12") (pin "1") (pinfunction "1_1") (pintype "passive"))
      (node (ref "R13") (pin "1") (pinfunction "1_1") (pintype "passive"))
      (node (ref "R3") (pin "1") (pinfunction "1_1") (pintype "passive"))
      (node (ref "R4") (pin "1") (pinfunction "1_1") (pintype "passive"))
      (node (ref "R5") (pin "1") (pinfunction "1_1") (pintype "passive"))
      (node (ref "R6") (pin "2") (pinfunction "2_2") (pintype "passive"))
      (node (ref "R8") (pin "1") (pinfunction "1_1") (pintype "passive"))
      (node (ref "R9") (pin "1") (pinfunction "1_1") (pintype "passive"))
      (node (ref "TRX2") (pin "VDD_IO") (pinfunction "VDD_IO_VDD_IO") (pintype "bidirectional"))
      (node (ref "U1") (pin "5") (pinfunction "VCC_5") (pintype "power_in"))
      (node (ref "U2") (pin "5") (pinfunction "VCC_5") (pintype "power_in"))
    )
    (net (code "71") (name "SPI_FM_CS") (class "Default")
      (node (ref "FM_SF") (pin "7") (pinfunction "S#_7") (pintype "input"))
      (node (ref "MCU_SF") (pin "22") (pinfunction "SEG21/VREF-/AN2/RP2/RA2_22") (pintype "bidirectional"))
      (node (ref "R9") (pin "2") (pinfunction "2_2") (pintype "passive"))
    )
    (net (code "72") (name "SPI_MISO") (class "Default")
      (node (ref "FM_SF") (pin "8") (pinfunction "DQ1_8") (pintype "input"))
      (node (ref "MCU_SF") (pin "23") (pinfunction "SEG18/AN1/RP1/RA1_23") (pintype "bidirectional"))
      (node (ref "R5") (pin "2") (pinfunction "2_2") (pintype "passive"))
    )
    (net (code "73") (name "SPI_MOSI") (class "Default")
      (node (ref "FM_SF") (pin "15") (pinfunction "DQ0_15") (pintype "input"))
      (node (ref "MCU_SF") (pin "24") (pinfunction "SEG19/AN0/AN1-/RP0/RA0_24") (pintype "bidirectional"))
      (node (ref "R8") (pin "2") (pinfunction "2_2") (pintype "passive"))
    )
    (net (code "74") (name "SPI_SCK") (class "Default")
      (node (ref "FM_SF") (pin "16") (pinfunction "C_16") (pintype "input"))
      (node (ref "MCU_SF") (pin "21") (pinfunction "VREF+/AN3/RP3/RA3_21") (pintype "bidirectional"))
      (node (ref "R11") (pin "2") (pinfunction "2_2") (pintype "passive"))
    )
    (net (code "75") (name "SUP_3V3_1") (class "Default")
      (node (ref "JP2") (pin "49") (pinfunction "49_49") (pintype "passive"))
      (node (ref "JP2") (pin "50") (pinfunction "50_50") (pintype "passive"))
    )
    (net (code "76") (name "SUP_3V3_2") (class "Default")
      (node (ref "JP2") (pin "25") (pinfunction "25_25") (pintype "passive"))
      (node (ref "JP2") (pin "26") (pinfunction "26_26") (pintype "passive"))
      (node (ref "OCP1") (pin "8") (pinfunction "IN_8") (pintype "bidirectional"))
      (node (ref "R10") (pin "1") (pinfunction "1_1") (pintype "passive"))
      (node (ref "R14") (pin "2") (pinfunction "2_2") (pintype "passive"))
    )
    (net (code "77") (name "SUP_5V0") (class "Default")
      (node (ref "JP2") (pin "15") (pinfunction "15_15") (pintype "passive"))
      (node (ref "JP2") (pin "16") (pinfunction "16_16") (pintype "passive"))
      (node (ref "OCP2") (pin "8") (pinfunction "IN_8") (pintype "bidirectional"))
      (node (ref "R18") (pin "1") (pinfunction "1_1") (pintype "passive"))
      (node (ref "R20") (pin "2") (pinfunction "2_2") (pintype "passive"))
    )
    (net (code "78") (name "TCXO_EN2") (class "Default")
      (node (ref "TCXO") (pin "P$4") (pinfunction "VCC_P$4") (pintype "power_in"))
      (node (ref "TRX2") (pin "TCXO_EN") (pinfunction "TCXO_EN_TCXO_EN") (pintype "bidirectional"))
    )
    (net (code "79") (name "TRX1") (class "Default")
      (node (ref "RFCON") (pin "P$1") (pinfunction "SGNL_P$1") (pintype "bidirectional"))
      (node (ref "TRX1") (pin "P$2") (pinfunction "ANT_P$2") (pintype "bidirectional"))
    )
    (net (code "80") (name "TRX1_AFOUT") (class "Default")
      (node (ref "C38") (pin "2") (pinfunction "2_2") (pintype "passive"))
      (node (ref "JP1") (pin "P$6") (pinfunction "P$6_P$6") (pintype "bidirectional"))
      (node (ref "TRX1") (pin "P$13") (pinfunction "AF_P$13") (pintype "bidirectional"))
    )
    (net (code "81") (name "TRX1_RXSELECT") (class "Default")
      (node (ref "IC2") (pin "1") (pinfunction "PCINT8/XCK0/T0_PB0_1") (pintype "bidirectional"))
      (node (ref "OPAMP") (pin "6") (pinfunction "-IN_6") (pintype "input"))
      (node (ref "R21") (pin "1") (pinfunction "1_1") (pintype "passive"))
      (node (ref "R36") (pin "1") (pinfunction "1_1") (pintype "passive"))
      (node (ref "TRX1") (pin "P$16") (pinfunction "RXSELECT_P$16") (pintype "bidirectional"))
    )
    (net (code "82") (name "TRX1_TXD") (class "Default")
      (node (ref "JP1") (pin "P$8") (pinfunction "P$8_P$8") (pintype "bidirectional"))
      (node (ref "OPAMP1") (pin "1") (pinfunction "OUT_1") (pintype "output"))
      (node (ref "R35") (pin "1") (pinfunction "1_1") (pintype "passive"))
      (node (ref "TRX1") (pin "P$14") (pinfunction "TXD_P$14") (pintype "bidirectional"))
    )
    (net (code "83") (name "TRX1_TXSELECT") (class "Default")
      (node (ref "JP1") (pin "P$10") (pinfunction "P$10_P$10") (pintype "bidirectional"))
      (node (ref "OPAMP") (pin "7") (pinfunction "OUT_7") (pintype "output"))
      (node (ref "TRX1") (pin "P$15") (pinfunction "TXSELECT_P$15") (pintype "bidirectional"))
    )
    (net (code "84") (name "TRX1{slash}TRX2") (class "Default")
      (node (ref "MCU_SF") (pin "46") (pinfunction "SEG9/RP14/CTED1/RB2_46") (pintype "bidirectional"))
    )
    (net (code "85") (name "TRX2_CS") (class "Default")
      (node (ref "MCU_SF") (pin "64") (pinfunction "LCDBIAS3/RP30/C_64") (pintype "bidirectional"))
    )
    (net (code "86") (name "TRX2_MOSI") (class "Default")
      (node (ref "JP1") (pin "P$12") (pinfunction "P$12_P$12") (pintype "bidirectional"))
      (node (ref "MCU_SF") (pin "60") (pinfunction "COM3/RP34/RE6_60") (pintype "bidirectional"))
      (node (ref "TRX2") (pin "MOSI") (pinfunction "MOSI_MOSI") (pintype "bidirectional"))
    )
    (net (code "87") (name "TRX2_RX{slash}TX") (class "Default")
      (node (ref "MCU_SF") (pin "47") (pinfunction "VLCAP2/RP9/RB1_47") (pintype "bidirectional"))
    )
    (net (code "88") (name "TRX2_TX{slash}RX") (class "Default")
      (node (ref "MCU_SF") (pin "48") (pinfunction "VLCAP1/RP8/CTED13/INT0/RB0_48") (pintype "bidirectional"))
    )
    (net (code "89") (name "unconnected-(FM_SF-DNU(1)-Pad4)") (class "Default")
      (node (ref "FM_SF") (pin "4") (pinfunction "DNU(1)_4") (pintype "input"))
    )
    (net (code "90") (name "unconnected-(FM_SF-DNU(2)-Pad5)") (class "Default")
      (node (ref "FM_SF") (pin "5") (pinfunction "DNU(2)_5") (pintype "input"))
    )
    (net (code "91") (name "unconnected-(FM_SF-DNU(3)-Pad6)") (class "Default")
      (node (ref "FM_SF") (pin "6") (pinfunction "DNU(3)_6") (pintype "input"))
    )
    (net (code "92") (name "unconnected-(FM_SF-DNU(4)-Pad11)") (class "Default")
      (node (ref "FM_SF") (pin "11") (pinfunction "DNU(4)_11") (pintype "input"))
    )
    (net (code "93") (name "unconnected-(FM_SF-DNU(5)-Pad12)") (class "Default")
      (node (ref "FM_SF") (pin "12") (pinfunction "DNU(5)_12") (pintype "input"))
    )
    (net (code "94") (name "unconnected-(FM_SF-DNU(6)-Pad13)") (class "Default")
      (node (ref "FM_SF") (pin "13") (pinfunction "DNU(6)_13") (pintype "input"))
    )
    (net (code "95") (name "unconnected-(FM_SF-DNU(7)-Pad14)") (class "Default")
      (node (ref "FM_SF") (pin "14") (pinfunction "DNU(7)_14") (pintype "input"))
    )
    (net (code "96") (name "unconnected-(IC2-PCINT3{slash}ADC3_PA3-Pad37)") (class "Default")
      (node (ref "IC2") (pin "37") (pinfunction "PCINT3/ADC3_PA3_37") (pintype "bidirectional"))
    )
    (net (code "97") (name "unconnected-(IC2-PCINT4{slash}ADC4_PA4-Pad36)") (class "Default")
      (node (ref "IC2") (pin "36") (pinfunction "PCINT4/ADC4_PA4_36") (pintype "bidirectional"))
    )
    (net (code "98") (name "unconnected-(IC2-PCINT5{slash}ADC5_PA5-Pad35)") (class "Default")
      (node (ref "IC2") (pin "35") (pinfunction "PCINT5/ADC5_PA5_35") (pintype "bidirectional"))
    )
    (net (code "99") (name "unconnected-(IC2-PCINT6{slash}ADC6_PA6-Pad34)") (class "Default")
      (node (ref "IC2") (pin "34") (pinfunction "PCINT6/ADC6_PA6_34") (pintype "bidirectional"))
    )
    (net (code "100") (name "unconnected-(IC2-PCINT12{slash}OC0B{slash}SS_PB4-Pad5)") (class "Default")
      (node (ref "IC2") (pin "5") (pinfunction "PCINT12/OC0B/SS_PB4_5") (pintype "bidirectional"))
    )
    (net (code "101") (name "unconnected-(IC2-PCINT13{slash}MOSI_PB5-Pad6)") (class "Default")
      (node (ref "IC2") (pin "6") (pinfunction "PCINT13/MOSI_PB5_6") (pintype "bidirectional"))
    )
    (net (code "102") (name "unconnected-(IC2-PCINT14{slash}MISO_PB6-Pad7)") (class "Default")
      (node (ref "IC2") (pin "7") (pinfunction "PCINT14/MISO_PB6_7") (pintype "bidirectional"))
    )
    (net (code "103") (name "unconnected-(IC2-PCINT15{slash}SCK_PB7-Pad8)") (class "Default")
      (node (ref "IC2") (pin "8") (pinfunction "PCINT15/SCK_PB7_8") (pintype "bidirectional"))
    )
    (net (code "104") (name "unconnected-(IC2-PCINT16{slash}SCL_PC0-Pad22)") (class "Default")
      (node (ref "IC2") (pin "22") (pinfunction "PCINT16/SCL_PC0_22") (pintype "bidirectional"))
    )
    (net (code "105") (name "unconnected-(IC2-PCINT17{slash}SDA_PC1-Pad23)") (class "Default")
      (node (ref "IC2") (pin "23") (pinfunction "PCINT17/SDA_PC1_23") (pintype "bidirectional"))
    )
    (net (code "106") (name "unconnected-(IC2-PCINT18{slash}TCK_PC2-Pad24)") (class "Default")
      (node (ref "IC2") (pin "24") (pinfunction "PCINT18/TCK_PC2_24") (pintype "bidirectional"))
    )
    (net (code "107") (name "unconnected-(IC2-PCINT19{slash}TMS_PC3-Pad25)") (class "Default")
      (node (ref "IC2") (pin "25") (pinfunction "PCINT19/TMS_PC3_25") (pintype "bidirectional"))
    )
    (net (code "108") (name "unconnected-(IC2-PCINT20{slash}TDO_PC4-Pad26)") (class "Default")
      (node (ref "IC2") (pin "26") (pinfunction "PCINT20/TDO_PC4_26") (pintype "bidirectional"))
    )
    (net (code "109") (name "unconnected-(IC2-PCINT21{slash}TDI_PC5-Pad27)") (class "Default")
      (node (ref "IC2") (pin "27") (pinfunction "PCINT21/TDI_PC5_27") (pintype "bidirectional"))
    )
    (net (code "110") (name "unconnected-(IC2-PCINT22{slash}TOSC1_PC6-Pad28)") (class "Default")
      (node (ref "IC2") (pin "28") (pinfunction "PCINT22/TOSC1_PC6_28") (pintype "bidirectional"))
    )
    (net (code "111") (name "unconnected-(IC2-PCINT23{slash}TOSC2_PC7-Pad29)") (class "Default")
      (node (ref "IC2") (pin "29") (pinfunction "PCINT23/TOSC2_PC7_29") (pintype "bidirectional"))
    )
    (net (code "112") (name "unconnected-(IC2-PCINT28{slash}OC1B_PD4-Pad18)") (class "Default")
      (node (ref "IC2") (pin "18") (pinfunction "PCINT28/OC1B_PD4_18") (pintype "bidirectional"))
    )
    (net (code "113") (name "unconnected-(IC2-PCINT30{slash}OC2B{slash}ICP_PD6-Pad20)") (class "Default")
      (node (ref "IC2") (pin "20") (pinfunction "PCINT30/OC2B/ICP_PD6_20") (pintype "bidirectional"))
    )
    (net (code "114") (name "unconnected-(IC2-PCINT31{slash}OC2A_PD7-Pad21)") (class "Default")
      (node (ref "IC2") (pin "21") (pinfunction "PCINT31/OC2A_PD7_21") (pintype "bidirectional"))
    )
    (net (code "115") (name "unconnected-(IC2-~{RESET}-Pad9)") (class "Default")
      (node (ref "IC2") (pin "9") (pinfunction "~{RESET}_9") (pintype "input"))
    )
    (net (code "116") (name "unconnected-(JP1-PadP$18)") (class "Default")
      (node (ref "JP1") (pin "P$18") (pinfunction "P$18_P$18") (pintype "bidirectional"))
    )
    (net (code "117") (name "unconnected-(JP1-PadP$20)") (class "Default")
      (node (ref "JP1") (pin "P$20") (pinfunction "P$20_P$20") (pintype "bidirectional"))
    )
    (net (code "118") (name "unconnected-(JP1-PadP$21)") (class "Default")
      (node (ref "JP1") (pin "P$21") (pinfunction "P$21_P$21") (pintype "bidirectional"))
    )
    (net (code "119") (name "unconnected-(JP1-PadP$22)") (class "Default")
      (node (ref "JP1") (pin "P$22") (pinfunction "P$22_P$22") (pintype "bidirectional"))
    )
    (net (code "120") (name "unconnected-(JP1-PadP$23)") (class "Default")
      (node (ref "JP1") (pin "P$23") (pinfunction "P$23_P$23") (pintype "bidirectional"))
    )
    (net (code "121") (name "unconnected-(JP1-PadP$24)") (class "Default")
      (node (ref "JP1") (pin "P$24") (pinfunction "P$24_P$24") (pintype "bidirectional"))
    )
    (net (code "122") (name "unconnected-(JP2-Pad4)") (class "Default")
      (node (ref "JP2") (pin "4") (pinfunction "4_4") (pintype "passive"))
    )
    (net (code "123") (name "unconnected-(JP2-Pad5)") (class "Default")
      (node (ref "JP2") (pin "5") (pinfunction "5_5") (pintype "passive"))
    )
    (net (code "124") (name "unconnected-(JP2-Pad6)") (class "Default")
      (node (ref "JP2") (pin "6") (pinfunction "6_6") (pintype "passive"))
    )
    (net (code "125") (name "unconnected-(JP2-Pad7)") (class "Default")
      (node (ref "JP2") (pin "7") (pinfunction "7_7") (pintype "passive"))
    )
    (net (code "126") (name "unconnected-(JP2-Pad8)") (class "Default")
      (node (ref "JP2") (pin "8") (pinfunction "8_8") (pintype "passive"))
    )
    (net (code "127") (name "unconnected-(JP2-Pad9)") (class "Default")
      (node (ref "JP2") (pin "9") (pinfunction "9_9") (pintype "passive"))
    )
    (net (code "128") (name "unconnected-(JP2-Pad10)") (class "Default")
      (node (ref "JP2") (pin "10") (pinfunction "10_10") (pintype "passive"))
    )
    (net (code "129") (name "unconnected-(JP2-Pad17)") (class "Default")
      (node (ref "JP2") (pin "17") (pinfunction "17_17") (pintype "passive"))
    )
    (net (code "130") (name "unconnected-(JP2-Pad18)") (class "Default")
      (node (ref "JP2") (pin "18") (pinfunction "18_18") (pintype "passive"))
    )
    (net (code "131") (name "unconnected-(JP2-Pad19)") (class "Default")
      (node (ref "JP2") (pin "19") (pinfunction "19_19") (pintype "passive"))
    )
    (net (code "132") (name "unconnected-(JP2-Pad20)") (class "Default")
      (node (ref "JP2") (pin "20") (pinfunction "20_20") (pintype "passive"))
    )
    (net (code "133") (name "unconnected-(JP2-Pad21)") (class "Default")
      (node (ref "JP2") (pin "21") (pinfunction "21_21") (pintype "passive"))
    )
    (net (code "134") (name "unconnected-(JP2-Pad22)") (class "Default")
      (node (ref "JP2") (pin "22") (pinfunction "22_22") (pintype "passive"))
    )
    (net (code "135") (name "unconnected-(JP2-Pad23)") (class "Default")
      (node (ref "JP2") (pin "23") (pinfunction "23_23") (pintype "passive"))
    )
    (net (code "136") (name "unconnected-(JP2-Pad24)") (class "Default")
      (node (ref "JP2") (pin "24") (pinfunction "24_24") (pintype "passive"))
    )
    (net (code "137") (name "unconnected-(JP2-Pad27)") (class "Default")
      (node (ref "JP2") (pin "27") (pinfunction "27_27") (pintype "passive"))
    )
    (net (code "138") (name "unconnected-(JP2-Pad28)") (class "Default")
      (node (ref "JP2") (pin "28") (pinfunction "28_28") (pintype "passive"))
    )
    (net (code "139") (name "unconnected-(JP2-Pad29)") (class "Default")
      (node (ref "JP2") (pin "29") (pinfunction "29_29") (pintype "passive"))
    )
    (net (code "140") (name "unconnected-(JP2-Pad30)") (class "Default")
      (node (ref "JP2") (pin "30") (pinfunction "30_30") (pintype "passive"))
    )
    (net (code "141") (name "unconnected-(JP2-Pad31)") (class "Default")
      (node (ref "JP2") (pin "31") (pinfunction "31_31") (pintype "passive"))
    )
    (net (code "142") (name "unconnected-(JP2-Pad32)") (class "Default")
      (node (ref "JP2") (pin "32") (pinfunction "32_32") (pintype "passive"))
    )
    (net (code "143") (name "unconnected-(JP2-Pad33)") (class "Default")
      (node (ref "JP2") (pin "33") (pinfunction "33_33") (pintype "passive"))
    )
    (net (code "144") (name "unconnected-(JP2-Pad34)") (class "Default")
      (node (ref "JP2") (pin "34") (pinfunction "34_34") (pintype "passive"))
    )
    (net (code "145") (name "unconnected-(JP2-Pad35)") (class "Default")
      (node (ref "JP2") (pin "35") (pinfunction "35_35") (pintype "passive"))
    )
    (net (code "146") (name "unconnected-(JP2-Pad36)") (class "Default")
      (node (ref "JP2") (pin "36") (pinfunction "36_36") (pintype "passive"))
    )
    (net (code "147") (name "unconnected-(JP2-Pad37)") (class "Default")
      (node (ref "JP2") (pin "37") (pinfunction "37_37") (pintype "passive"))
    )
    (net (code "148") (name "unconnected-(JP2-Pad38)") (class "Default")
      (node (ref "JP2") (pin "38") (pinfunction "38_38") (pintype "passive"))
    )
    (net (code "149") (name "unconnected-(JP2-Pad39)") (class "Default")
      (node (ref "JP2") (pin "39") (pinfunction "39_39") (pintype "passive"))
    )
    (net (code "150") (name "unconnected-(JP2-Pad40)") (class "Default")
      (node (ref "JP2") (pin "40") (pinfunction "40_40") (pintype "passive"))
    )
    (net (code "151") (name "unconnected-(JP2-Pad41)") (class "Default")
      (node (ref "JP2") (pin "41") (pinfunction "41_41") (pintype "passive"))
    )
    (net (code "152") (name "unconnected-(JP2-Pad42)") (class "Default")
      (node (ref "JP2") (pin "42") (pinfunction "42_42") (pintype "passive"))
    )
    (net (code "153") (name "unconnected-(JP2-Pad45)") (class "Default")
      (node (ref "JP2") (pin "45") (pinfunction "45_45") (pintype "passive"))
    )
    (net (code "154") (name "unconnected-(JP2-Pad46)") (class "Default")
      (node (ref "JP2") (pin "46") (pinfunction "46_46") (pintype "passive"))
    )
    (net (code "155") (name "unconnected-(JP2-Pad47)") (class "Default")
      (node (ref "JP2") (pin "47") (pinfunction "47_47") (pintype "passive"))
    )
    (net (code "156") (name "unconnected-(JP2-Pad48)") (class "Default")
      (node (ref "JP2") (pin "48") (pinfunction "48_48") (pintype "passive"))
    )
    (net (code "157") (name "unconnected-(MCU_SF-COM0{slash}RP33{slash}REFO1{slash}RE3-Pad63)") (class "Default")
      (node (ref "MCU_SF") (pin "63") (pinfunction "COM0/RP33/REFO1/RE3_63") (pintype "bidirectional"))
    )
    (net (code "158") (name "unconnected-(MCU_SF-COM1{slash}RP32{slash}RE4-Pad62)") (class "Default")
      (node (ref "MCU_SF") (pin "62") (pinfunction "COM1/RP32/RE4_62") (pintype "bidirectional"))
    )
    (net (code "159") (name "unconnected-(MCU_SF-COM2{slash}RP37{slash}RE5-Pad61)") (class "Default")
      (node (ref "MCU_SF") (pin "61") (pinfunction "COM2/RP37/RE5_61") (pintype "bidirectional"))
    )
    (net (code "160") (name "unconnected-(MCU_SF-COM5{slash}SEG29{slash}AN19{slash}RP39{slash}RG1-Pad4)") (class "Default")
      (node (ref "MCU_SF") (pin "4") (pinfunction "COM5/SEG29/AN19/RP39/RG1_4") (pintype "bidirectional"))
    )
    (net (code "161") (name "unconnected-(MCU_SF-COM6{slash}SEG30{slash}AN18{slash}C3INA{slash}RP42{slash}RG2-Pad5)") (class "Default")
      (node (ref "MCU_SF") (pin "5") (pinfunction "COM6/SEG30/AN18/C3INA/RP42/RG2_5") (pintype "bidirectional"))
    )
    (net (code "162") (name "unconnected-(MCU_SF-COM7{slash}SEG31{slash}AN17{slash}C3INB{slash}RP43{slash}RG3-Pad6)") (class "Default")
      (node (ref "MCU_SF") (pin "6") (pinfunction "COM7/SEG31/AN17/C3INB/RP43/RG3_6") (pintype "bidirectional"))
    )
    (net (code "163") (name "unconnected-(MCU_SF-LCDBIAS0{slash}RP31{slash}RE7-Pad59)") (class "Default")
      (node (ref "MCU_SF") (pin "59") (pinfunction "LCDBIAS0/RP31/RE7_59") (pintype "bidirectional"))
    )
    (net (code "164") (name "unconnected-(MCU_SF-SEG0{slash}RP20{slash}PSP0{slash}RD0-Pad58)") (class "Default")
      (node (ref "MCU_SF") (pin "58") (pinfunction "SEG0/RP20/PSP0/RD0_58") (pintype "bidirectional"))
    )
    (net (code "165") (name "unconnected-(MCU_SF-SEG1{slash}RP21{slash}PSP1{slash}RD1-Pad55)") (class "Default")
      (node (ref "MCU_SF") (pin "55") (pinfunction "SEG1/RP21/PSP1/RD1_55") (pintype "bidirectional"))
    )
    (net (code "166") (name "unconnected-(MCU_SF-SEG2{slash}RP22{slash}PSP2{slash}RD2-Pad54)") (class "Default")
      (node (ref "MCU_SF") (pin "54") (pinfunction "SEG2/RP22/PSP2/RD2_54") (pintype "bidirectional"))
    )
    (net (code "167") (name "unconnected-(MCU_SF-SEG3{slash}RP23{slash}PSP3{slash}RD3-Pad53)") (class "Default")
      (node (ref "MCU_SF") (pin "53") (pinfunction "SEG3/RP23/PSP3/RD3_53") (pintype "bidirectional"))
    )
    (net (code "168") (name "unconnected-(MCU_SF-SEG4{slash}RP24{slash}PSP4{slash}RD4-Pad52)") (class "Default")
      (node (ref "MCU_SF") (pin "52") (pinfunction "SEG4/RP24/PSP4/RD4_52") (pintype "bidirectional"))
    )
    (net (code "169") (name "unconnected-(MCU_SF-SEG5{slash}SDA2{slash}RP25{slash}PSP5{slash}RD5-Pad51)") (class "Default")
      (node (ref "MCU_SF") (pin "51") (pinfunction "SEG5/SDA2/RP25/PSP5/RD5_51") (pintype "bidirectional"))
    )
    (net (code "170") (name "unconnected-(MCU_SF-SEG6{slash}SCL2{slash}RP26{slash}PSP6{slash}RD6-Pad50)") (class "Default")
      (node (ref "MCU_SF") (pin "50") (pinfunction "SEG6/SCL2/RP26/PSP6/RD6_50") (pintype "bidirectional"))
    )
    (net (code "171") (name "unconnected-(MCU_SF-SEG7{slash}RP27{slash}REFO2{slash}PSP7{slash}RD7-Pad49)") (class "Default")
      (node (ref "MCU_SF") (pin "49") (pinfunction "SEG7/RP27/REFO2/PSP7/RD7_49") (pintype "bidirectional"))
    )
    (net (code "172") (name "unconnected-(MCU_SF-SEG8{slash}RP13{slash}CTED4{slash}RB5-Pad43)") (class "Default")
      (node (ref "MCU_SF") (pin "43") (pinfunction "SEG8/RP13/CTED4/RB5_43") (pintype "bidirectional"))
    )
    (net (code "173") (name "unconnected-(MCU_SF-SEG10{slash}RP7{slash}CTED2{slash}RB3-Pad45)") (class "Default")
      (node (ref "MCU_SF") (pin "45") (pinfunction "SEG10/RP7/CTED2/RB3_45") (pintype "bidirectional"))
    )
    (net (code "174") (name "unconnected-(MCU_SF-SEG11{slash}RP12{slash}CTED3{slash}RB4-Pad44)") (class "Default")
      (node (ref "MCU_SF") (pin "44") (pinfunction "SEG11/RP12/CTED3/RB4_44") (pintype "bidirectional"))
    )
    (net (code "175") (name "unconnected-(MCU_SF-SEG12{slash}RP16{slash}CTED10{slash}RC5-Pad36)") (class "Default")
      (node (ref "MCU_SF") (pin "36") (pinfunction "SEG12/RP16/CTED10/RC5_36") (pintype "bidirectional"))
    )
    (net (code "176") (name "unconnected-(MCU_SF-SEG13{slash}AN9{slash}RP11{slash}CTED7{slash}RC2-Pad33)") (class "Default")
      (node (ref "MCU_SF") (pin "33") (pinfunction "SEG13/AN9/RP11/CTED7/RC2_33") (pintype "bidirectional"))
    )
    (net (code "177") (name "unconnected-(MCU_SF-SEG14{slash}AN6{slash}RP4{slash}RA4-Pad28)") (class "Default")
      (node (ref "MCU_SF") (pin "28") (pinfunction "SEG14/AN6/RP4/RA4_28") (pintype "bidirectional"))
    )
    (net (code "178") (name "unconnected-(MCU_SF-SEG16{slash}SDA1{slash}RP17{slash}CTED9{slash}RC4-Pad35)") (class "Default")
      (node (ref "MCU_SF") (pin "35") (pinfunction "SEG16/SDA1/RP17/CTED9/RC4_35") (pintype "bidirectional"))
    )
    (net (code "179") (name "unconnected-(MCU_SF-SEG17{slash}SCL1{slash}RP15{slash}CTED8{slash}RC3-Pad34)") (class "Default")
      (node (ref "MCU_SF") (pin "34") (pinfunction "SEG17/SCL1/RP15/CTED8/RC3_34") (pintype "bidirectional"))
    )
    (net (code "180") (name "unconnected-(MCU_SF-SEG20{slash}AN7{slash}CTMUI{slash}C2INB{slash}RP36{slash}RF2-Pad16)") (class "Default")
      (node (ref "MCU_SF") (pin "16") (pinfunction "SEG20/AN7/CTMUI/C2INB/RP36/RF2_16") (pintype "bidirectional"))
    )
    (net (code "181") (name "unconnected-(MCU_SF-SEG23{slash}CVREF{slash}AN10{slash}C1INB{slash}RP35{slash}RF5-Pad13)") (class "Default")
      (node (ref "MCU_SF") (pin "13") (pinfunction "SEG23/CVREF/AN10/C1INB/RP35/RF5_13") (pintype "bidirectional"))
    )
    (net (code "182") (name "unconnected-(MCU_SF-SEG24{slash}AN11{slash}C1INA{slash}RP40{slash}RF6-Pad12)") (class "Default")
      (node (ref "MCU_SF") (pin "12") (pinfunction "SEG24/AN11/C1INA/RP40/RF6_12") (pintype "bidirectional"))
    )
    (net (code "183") (name "unconnected-(MCU_SF-SEG25{slash}AN5{slash}RP38{slash}RF7-Pad11)") (class "Default")
      (node (ref "MCU_SF") (pin "11") (pinfunction "SEG25/AN5/RP38/RF7_11") (pintype "bidirectional"))
    )
    (net (code "184") (name "unconnected-(MCU_SF-SEG26{slash}AN16{slash}C3INC{slash}RP44{slash}RTCC{slash}RG4-Pad8)") (class "Default")
      (node (ref "MCU_SF") (pin "8") (pinfunction "SEG26/AN16/C3INC/RP44/RTCC/RG4_8") (pintype "bidirectional"))
    )
    (net (code "185") (name "unconnected-(MCU_SF-SOSCI{slash}RC1-Pad29)") (class "Default")
      (node (ref "MCU_SF") (pin "29") (pinfunction "SOSCI/RC1_29") (pintype "bidirectional"))
    )
    (net (code "186") (name "unconnected-(MCU_SF-SOSCO{slash}SCLKI{slash}PWRLCLK{slash}RC0-Pad30)") (class "Default")
      (node (ref "MCU_SF") (pin "30") (pinfunction "SOSCO/SCLKI/PWRLCLK/RC0_30") (pintype "bidirectional"))
    )
    (net (code "187") (name "unconnected-(MCU_SF-VBAT-Pad18)") (class "Default")
      (node (ref "MCU_SF") (pin "18") (pinfunction "VBAT_18") (pintype "bidirectional"))
    )
    (net (code "188") (name "unconnected-(MOS1-D2-Pad3)") (class "Default")
      (node (ref "MOS1") (pin "3") (pinfunction "D2_3") (pintype "input"))
    )
    (net (code "189") (name "unconnected-(MOS1-G2-Pad5)") (class "Default")
      (node (ref "MOS1") (pin "5") (pinfunction "G2_5") (pintype "input"))
    )
    (net (code "190") (name "unconnected-(MOS1-S2-Pad4)") (class "Default")
      (node (ref "MOS1") (pin "4") (pinfunction "S2_4") (pintype "input"))
    )
    (net (code "191") (name "unconnected-(MOS2-D2-Pad3)") (class "Default")
      (node (ref "MOS2") (pin "3") (pinfunction "D2_3") (pintype "input"))
    )
    (net (code "192") (name "unconnected-(MOS2-G2-Pad5)") (class "Default")
      (node (ref "MOS2") (pin "5") (pinfunction "G2_5") (pintype "input"))
    )
    (net (code "193") (name "unconnected-(MOS2-S2-Pad4)") (class "Default")
      (node (ref "MOS2") (pin "4") (pinfunction "S2_4") (pintype "input"))
    )
    (net (code "194") (name "unconnected-(OCP1-GATEP-Pad2)") (class "Default")
      (node (ref "OCP1") (pin "2") (pinfunction "GATEP_2") (pintype "bidirectional"))
    )
    (net (code "195") (name "unconnected-(OCP1-PWRGD-Pad5)") (class "Default")
      (node (ref "OCP1") (pin "5") (pinfunction "PWRGD_5") (pintype "bidirectional"))
    )
    (net (code "196") (name "unconnected-(OCP2-GATEP-Pad2)") (class "Default")
      (node (ref "OCP2") (pin "2") (pinfunction "GATEP_2") (pintype "bidirectional"))
    )
    (net (code "197") (name "unconnected-(OCP2-PWRGD-Pad5)") (class "Default")
      (node (ref "OCP2") (pin "5") (pinfunction "PWRGD_5") (pintype "bidirectional"))
    )
    (net (code "198") (name "unconnected-(TRX1-NC1-PadP$4)") (class "Default")
      (node (ref "TRX1") (pin "P$4") (pinfunction "NC1_P$4") (pintype "bidirectional"))
    )
    (net (code "199") (name "unconnected-(TRX1-NC2-PadP$5)") (class "Default")
      (node (ref "TRX1") (pin "P$5") (pinfunction "NC2_P$5") (pintype "bidirectional"))
    )
    (net (code "200") (name "unconnected-(TRX1-NC3-PadP$6)") (class "Default")
      (node (ref "TRX1") (pin "P$6") (pinfunction "NC3_P$6") (pintype "bidirectional"))
    )
    (net (code "201") (name "unconnected-(TRX1-NC4-PadP$7)") (class "Default")
      (node (ref "TRX1") (pin "P$7") (pinfunction "NC4_P$7") (pintype "bidirectional"))
    )
    (net (code "202") (name "unconnected-(TRX1-NC5-PadP$8)") (class "Default")
      (node (ref "TRX1") (pin "P$8") (pinfunction "NC5_P$8") (pintype "bidirectional"))
    )
    (net (code "203") (name "unconnected-(TRX1-RXD-PadP$12)") (class "Default")
      (node (ref "TRX1") (pin "P$12") (pinfunction "RXD_P$12") (pintype "bidirectional"))
    )
    (net (code "204") (name "unconnected-(TRX2-PadCLK)") (class "Default")
      (node (ref "TRX2") (pin "CLK") (pinfunction "CLK_CLK") (pintype "bidirectional"))
    )
    (net (code "205") (name "unconnected-(TRX2-PadCLK16N)") (class "Default")
      (node (ref "TRX2") (pin "CLK16N") (pinfunction "CLK16N_CLK16N") (pintype "bidirectional"))
    )
    (net (code "206") (name "unconnected-(TRX2-PadFILT)") (class "Default")
      (node (ref "TRX2") (pin "FILT") (pinfunction "FILT_FILT") (pintype "bidirectional"))
    )
    (net (code "207") (name "unconnected-(TRX2-PadIRQ)") (class "Default")
      (node (ref "TRX2") (pin "IRQ") (pinfunction "IRQ_IRQ") (pintype "bidirectional"))
    )
    (net (code "208") (name "unconnected-(TRX2-PadMISO)") (class "Default")
      (node (ref "TRX2") (pin "MISO") (pinfunction "MISO_MISO") (pintype "bidirectional"))
    )
    (net (code "209") (name "unconnected-(TRX2-PadSEL)") (class "Default")
      (node (ref "TRX2") (pin "SEL") (pinfunction "SEL_SEL") (pintype "bidirectional"))
    )
    (net (code "210") (name "unconnected-(TRX2-PadSYSCLK)") (class "Default")
      (node (ref "TRX2") (pin "SYSCLK") (pinfunction "SYSCLK_SYSCLK") (pintype "bidirectional"))
    )
  )
)
